# homeboard4.net
KiCad netlist of a schematic drawn in EAGLE
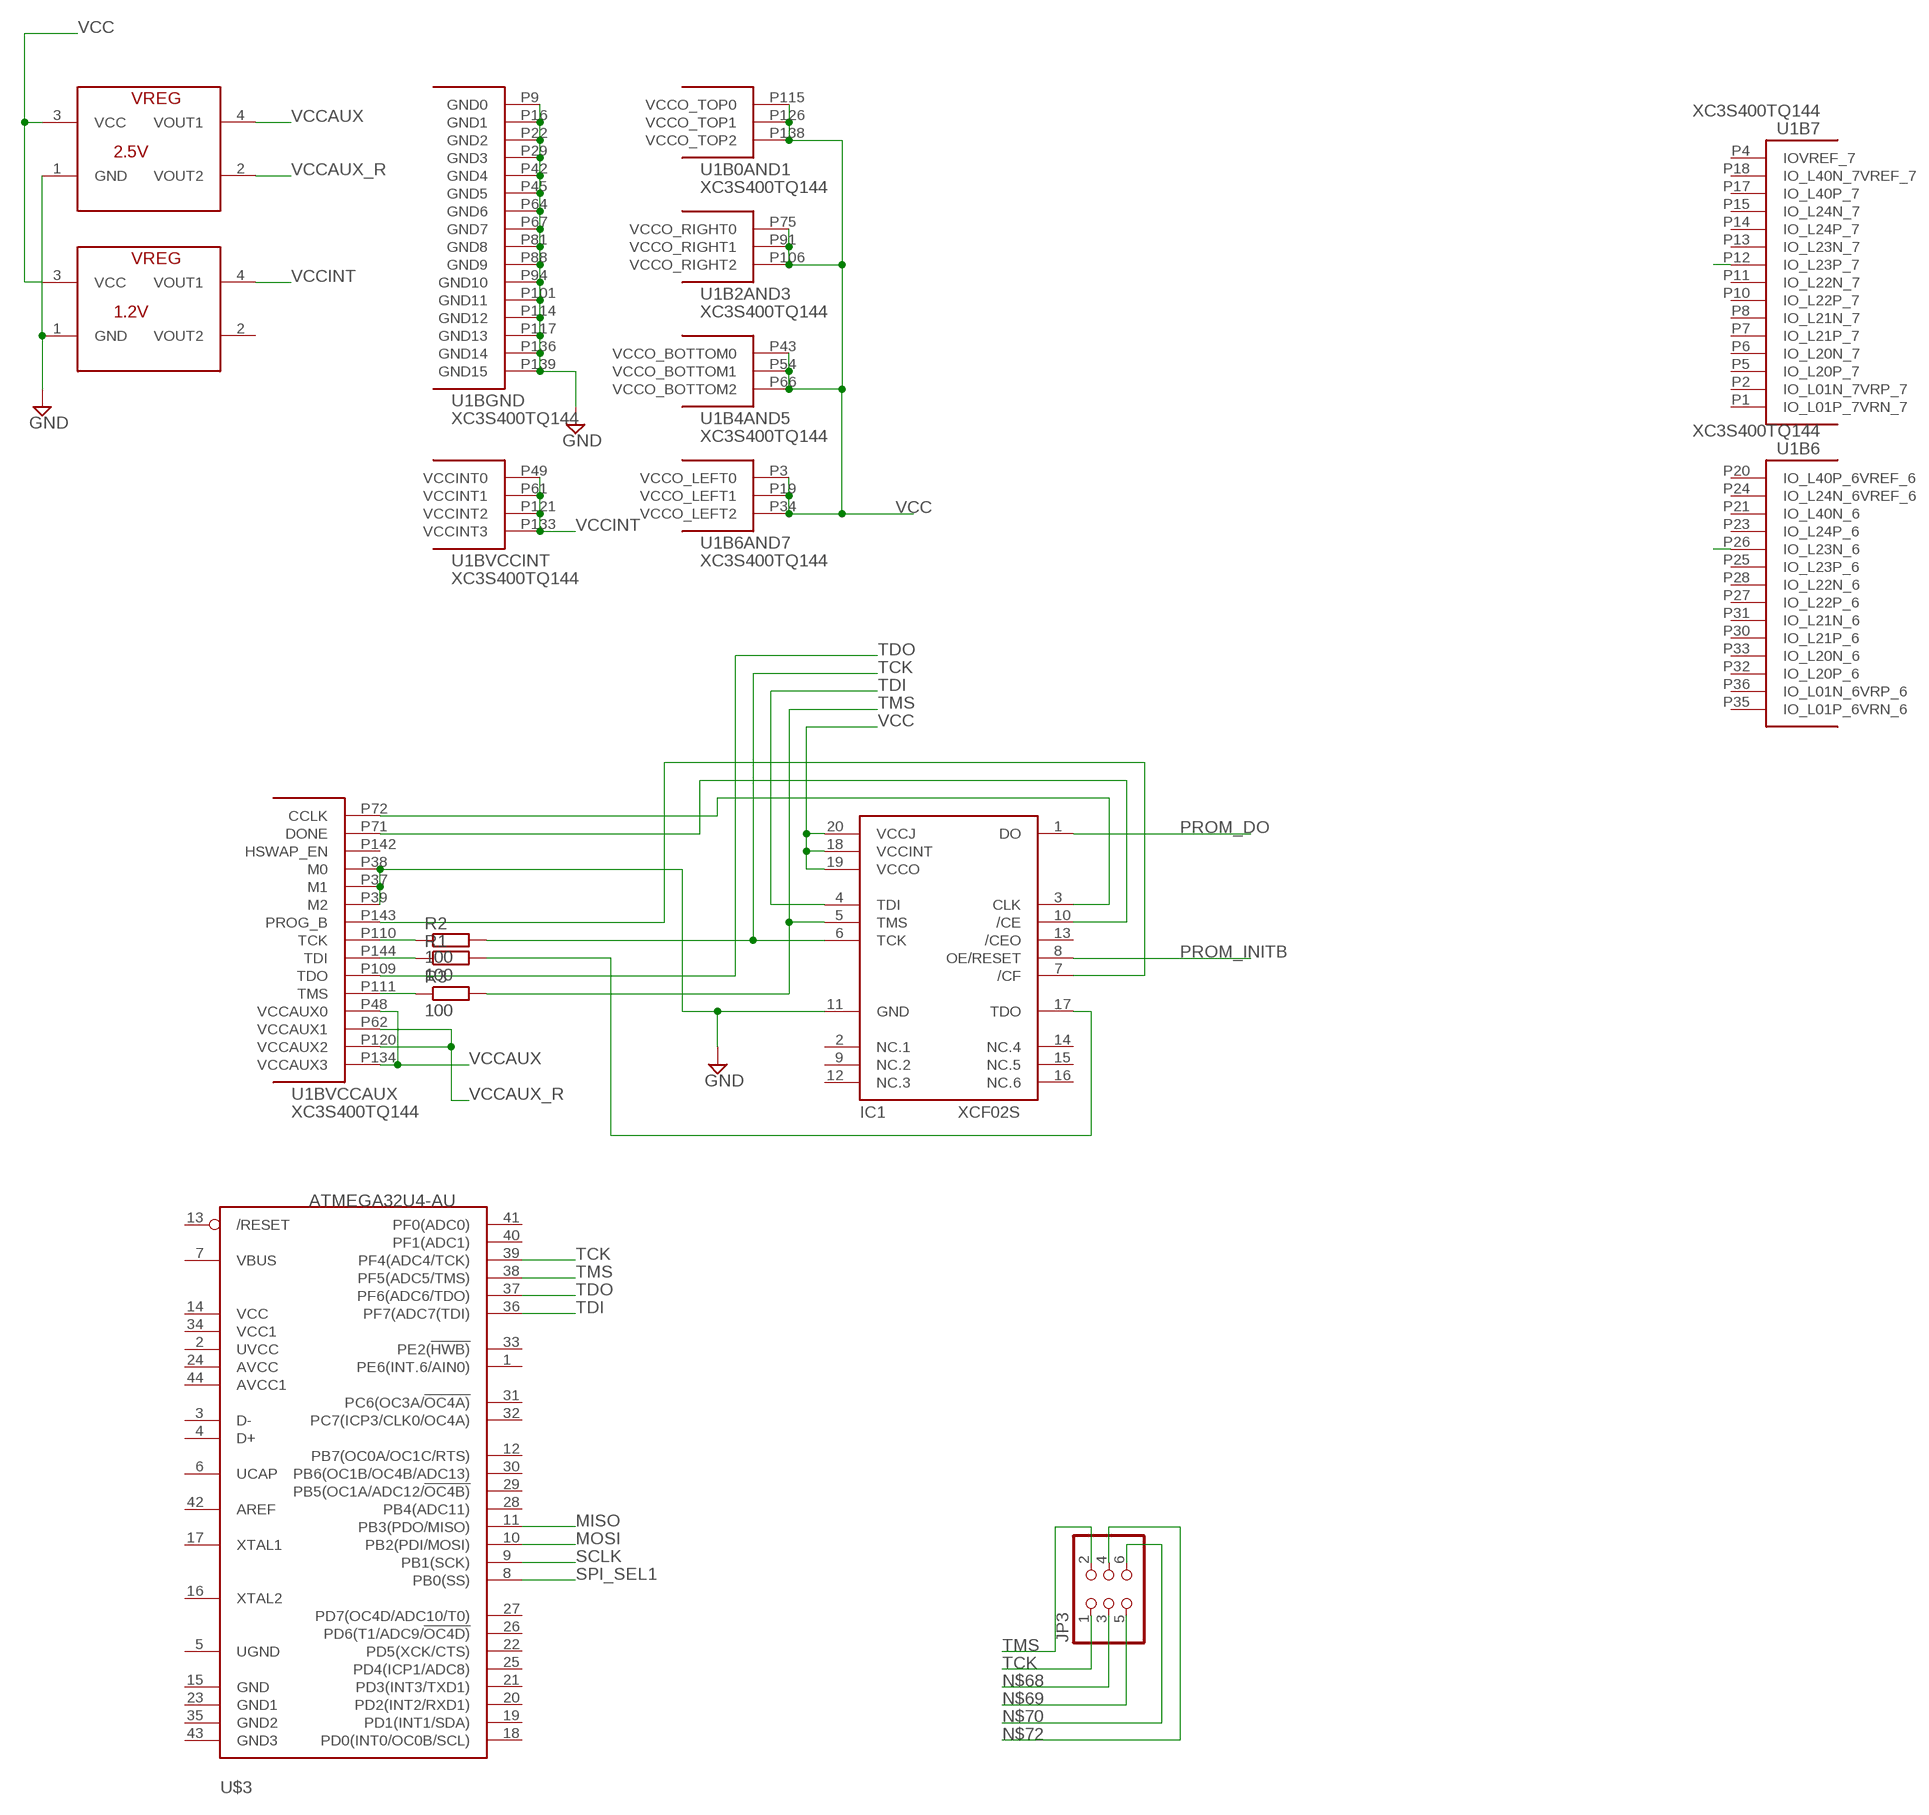
[diagram p0: schematic, sheet 1, part 1 of 3]
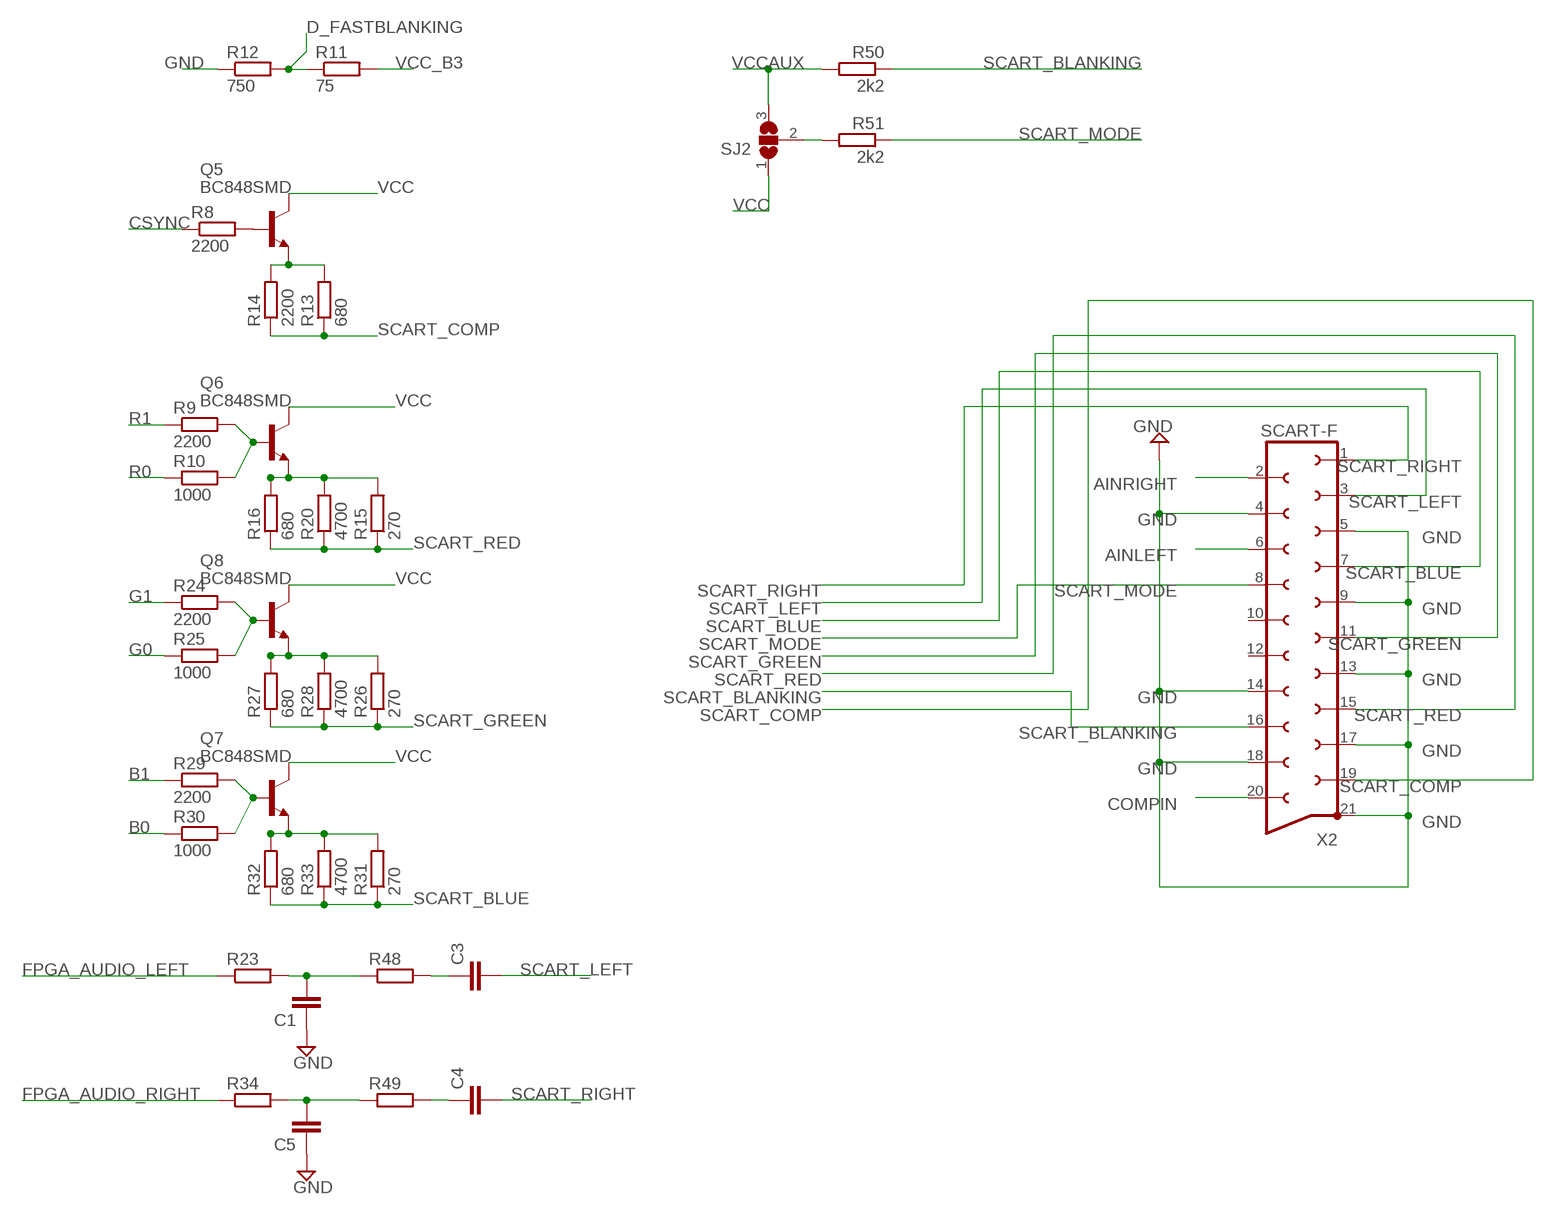
[diagram p1: schematic, sheet 1, part 2 of 3]
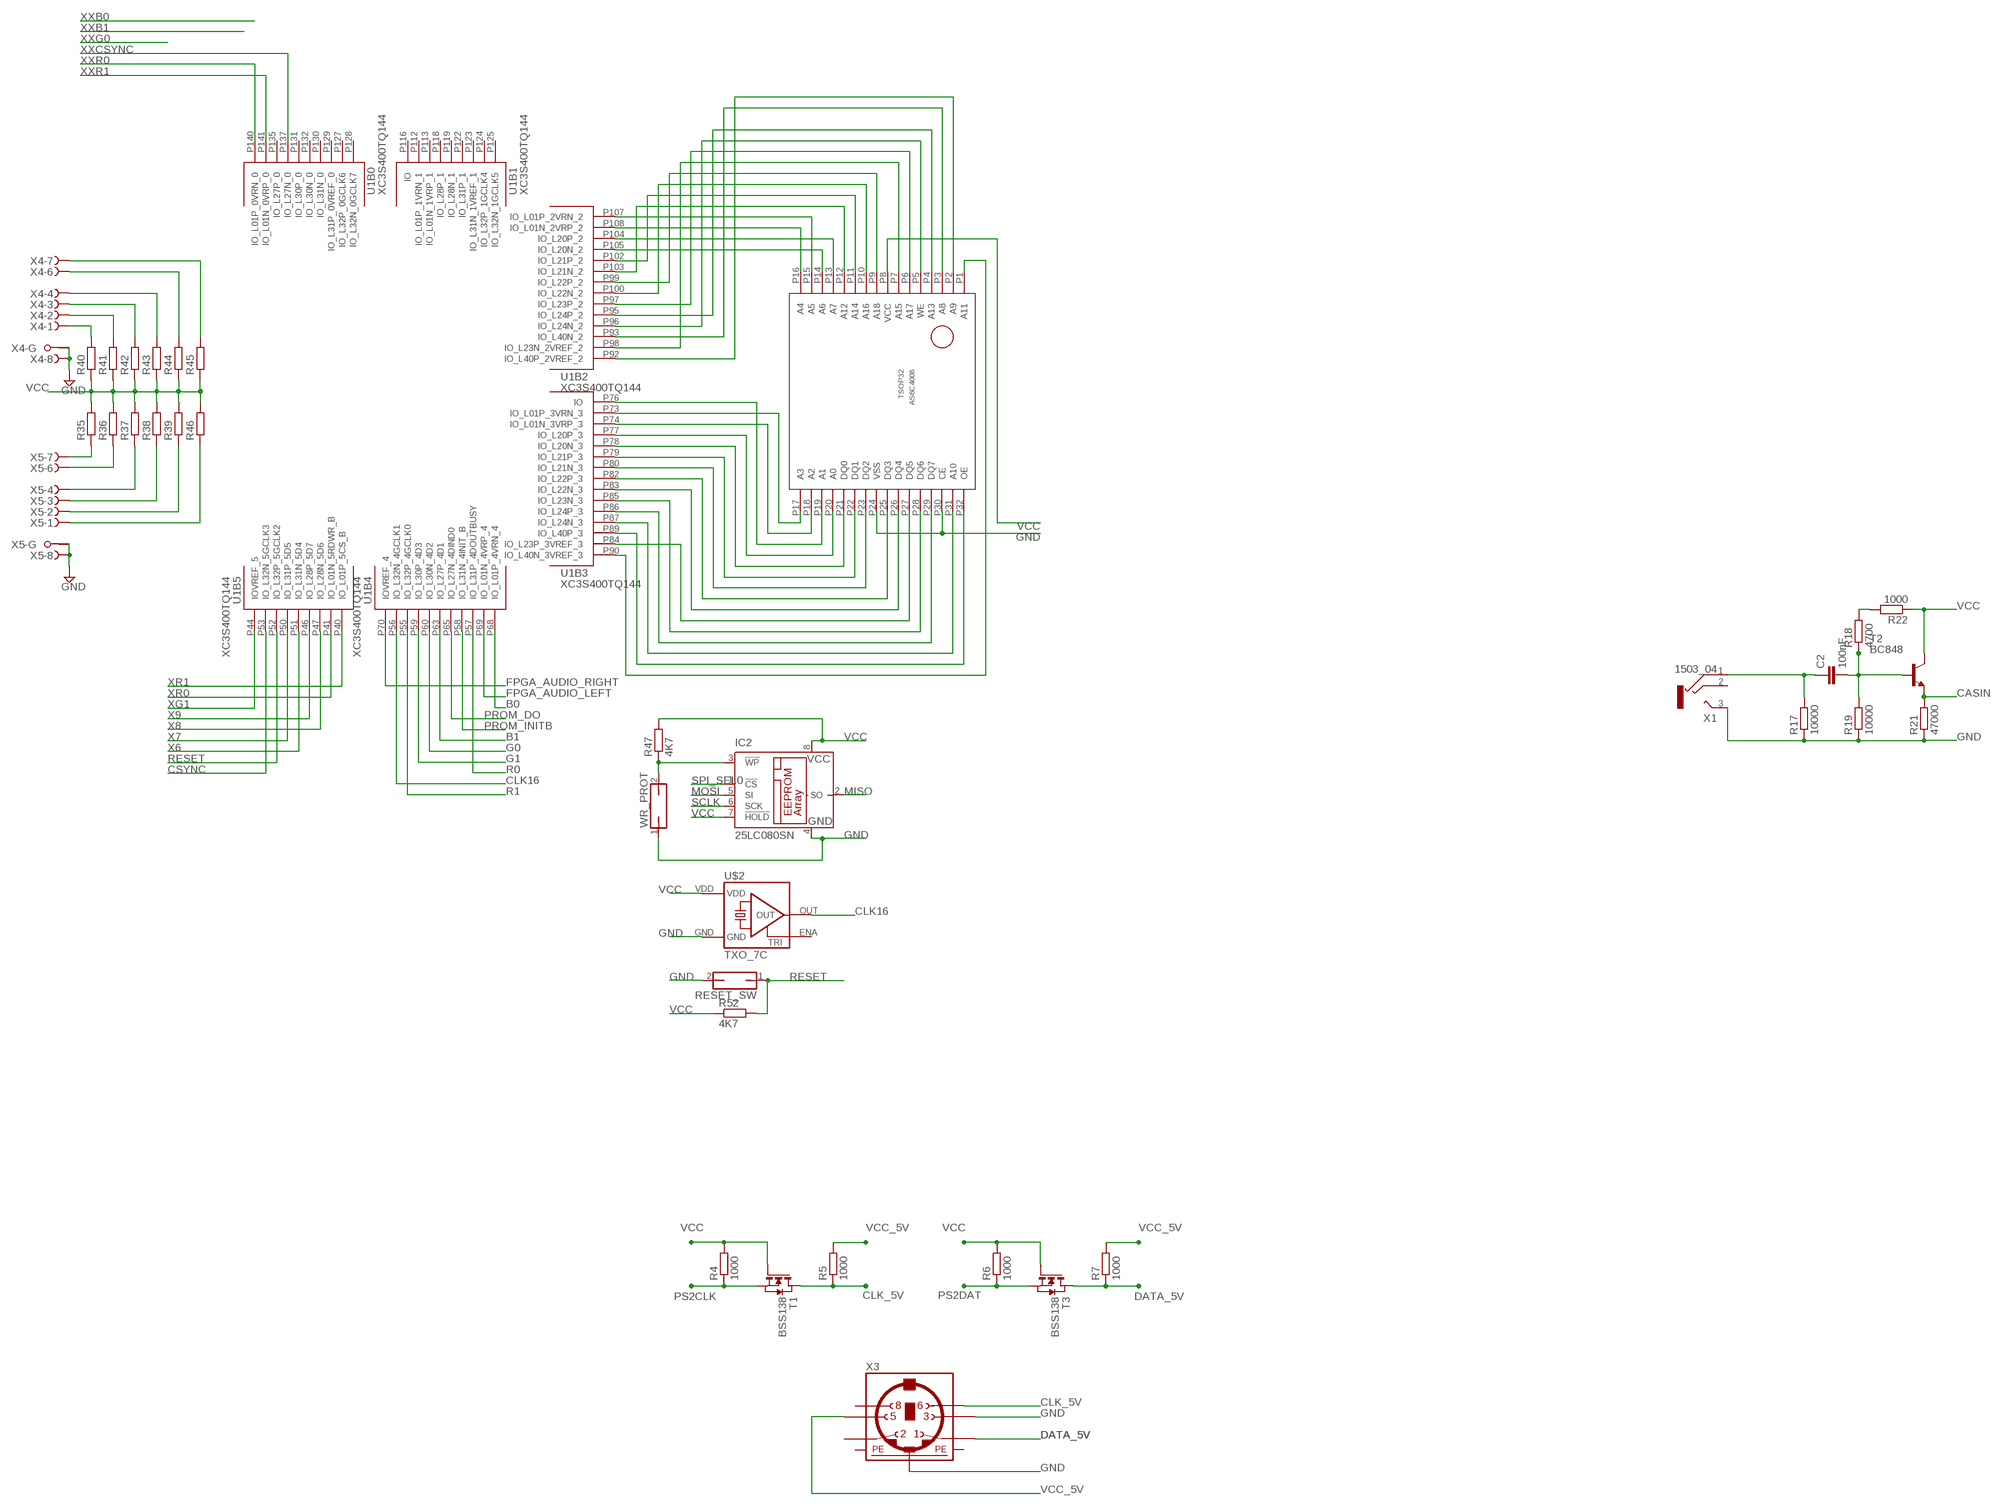
[diagram p2: schematic, sheet 1, part 3 of 3]

(export (version "E")
  (design (tool "Eeschema 10.0.6"))
  (components
    (comp (ref "C1")
      (value "C-EUC0603")
      (footprint "eagle-import:C0603")
      (libsource (lib "eagle-import") (part "C-EUC0603"))
    )
    (comp (ref "C2")
      (value "100nF")
      (footprint "eagle-import:C0603")
      (libsource (lib "eagle-import") (part "C-EUC0603"))
    )
    (comp (ref "C3")
      (value "C-EUC0603")
      (footprint "eagle-import:C0603")
      (libsource (lib "eagle-import") (part "C-EUC0603"))
    )
    (comp (ref "C4")
      (value "C-EUC0603")
      (footprint "eagle-import:C0603")
      (libsource (lib "eagle-import") (part "C-EUC0603"))
    )
    (comp (ref "C5")
      (value "C-EUC0603")
      (footprint "eagle-import:C0603")
      (libsource (lib "eagle-import") (part "C-EUC0603"))
    )
    (comp (ref "IC1")
      (value "XCF02S")
      (footprint "eagle-import:VO20")
      (libsource (lib "eagle-import") (part "XCF02S"))
    )
    (comp (ref "IC2")
      (value "25LC080SN")
      (footprint "eagle-import:SO-08")
      (fields (field (name "MF") "MICROCHIP") (field (name "MPN") "25LC080/SN"))
      (libsource (lib "eagle-import") (part "25SNLC080"))
    )
    (comp (ref "JP3")
      (value "PINHD-2X3")
      (footprint "eagle-import:2X03")
      (libsource (lib "eagle-import") (part "PINHD-2X3"))
    )
    (comp (ref "Q5")
      (value "BC848SMD")
      (footprint "eagle-import:SOT23")
      (libsource (lib "eagle-import") (part "BC848SMD"))
    )
    (comp (ref "Q6")
      (value "BC848SMD")
      (footprint "eagle-import:SOT23")
      (libsource (lib "eagle-import") (part "BC848SMD"))
    )
    (comp (ref "Q7")
      (value "BC848SMD")
      (footprint "eagle-import:SOT23")
      (libsource (lib "eagle-import") (part "BC848SMD"))
    )
    (comp (ref "Q8")
      (value "BC848SMD")
      (footprint "eagle-import:SOT23")
      (libsource (lib "eagle-import") (part "BC848SMD"))
    )
    (comp (ref "R1")
      (value "100")
      (footprint "eagle-import:R0805")
      (libsource (lib "eagle-import") (part "R-EU_R0805"))
    )
    (comp (ref "R2")
      (value "100")
      (footprint "eagle-import:R0805")
      (libsource (lib "eagle-import") (part "R-EU_R0805"))
    )
    (comp (ref "R3")
      (value "100")
      (footprint "eagle-import:R0805")
      (libsource (lib "eagle-import") (part "R-EU_R0805"))
    )
    (comp (ref "R4")
      (value "1000")
      (footprint "eagle-import:R0805")
      (libsource (lib "eagle-import") (part "R-EU_R0805"))
    )
    (comp (ref "R5")
      (value "1000")
      (footprint "eagle-import:R0805")
      (libsource (lib "eagle-import") (part "R-EU_R0805"))
    )
    (comp (ref "R6")
      (value "1000")
      (footprint "eagle-import:R0805")
      (libsource (lib "eagle-import") (part "R-EU_R0805"))
    )
    (comp (ref "R7")
      (value "1000")
      (footprint "eagle-import:R0805")
      (libsource (lib "eagle-import") (part "R-EU_R0805"))
    )
    (comp (ref "R8")
      (value "2200")
      (footprint "eagle-import:R0805")
      (libsource (lib "eagle-import") (part "R-EU_R0805"))
    )
    (comp (ref "R9")
      (value "2200")
      (footprint "eagle-import:R0805")
      (libsource (lib "eagle-import") (part "R-EU_R0805"))
    )
    (comp (ref "R10")
      (value "1000")
      (footprint "eagle-import:R0805")
      (libsource (lib "eagle-import") (part "R-EU_R0805"))
    )
    (comp (ref "R11")
      (value "75")
      (footprint "eagle-import:R0805")
      (libsource (lib "eagle-import") (part "R-EU_R0805"))
    )
    (comp (ref "R12")
      (value "750")
      (footprint "eagle-import:R0805")
      (libsource (lib "eagle-import") (part "R-EU_R0805"))
    )
    (comp (ref "R13")
      (value "680")
      (footprint "eagle-import:R0805")
      (libsource (lib "eagle-import") (part "R-EU_R0805"))
    )
    (comp (ref "R14")
      (value "2200")
      (footprint "eagle-import:R0805")
      (libsource (lib "eagle-import") (part "R-EU_R0805"))
    )
    (comp (ref "R15")
      (value "270")
      (footprint "eagle-import:R0805")
      (libsource (lib "eagle-import") (part "R-EU_R0805"))
    )
    (comp (ref "R16")
      (value "680")
      (footprint "eagle-import:R0805")
      (libsource (lib "eagle-import") (part "R-EU_R0805"))
    )
    (comp (ref "R17")
      (value "10000")
      (footprint "eagle-import:R0805")
      (libsource (lib "eagle-import") (part "R-EU_R0805"))
    )
    (comp (ref "R18")
      (value "4700")
      (footprint "eagle-import:R0805")
      (libsource (lib "eagle-import") (part "R-EU_R0805"))
    )
    (comp (ref "R19")
      (value "10000")
      (footprint "eagle-import:R0805")
      (libsource (lib "eagle-import") (part "R-EU_R0805"))
    )
    (comp (ref "R20")
      (value "4700")
      (footprint "eagle-import:R0805")
      (libsource (lib "eagle-import") (part "R-EU_R0805"))
    )
    (comp (ref "R21")
      (value "47000")
      (footprint "eagle-import:R0805")
      (libsource (lib "eagle-import") (part "R-EU_R0805"))
    )
    (comp (ref "R22")
      (value "1000")
      (footprint "eagle-import:R0805")
      (libsource (lib "eagle-import") (part "R-EU_R0805"))
    )
    (comp (ref "R23")
      (value "R-EU_M0805")
      (footprint "eagle-import:M0805")
      (libsource (lib "eagle-import") (part "resistor_R-EU_M0805"))
    )
    (comp (ref "R24")
      (value "2200")
      (footprint "eagle-import:R0805")
      (libsource (lib "eagle-import") (part "R-EU_R0805"))
    )
    (comp (ref "R25")
      (value "1000")
      (footprint "eagle-import:R0805")
      (libsource (lib "eagle-import") (part "R-EU_R0805"))
    )
    (comp (ref "R26")
      (value "270")
      (footprint "eagle-import:R0805")
      (libsource (lib "eagle-import") (part "R-EU_R0805"))
    )
    (comp (ref "R27")
      (value "680")
      (footprint "eagle-import:R0805")
      (libsource (lib "eagle-import") (part "R-EU_R0805"))
    )
    (comp (ref "R28")
      (value "4700")
      (footprint "eagle-import:R0805")
      (libsource (lib "eagle-import") (part "R-EU_R0805"))
    )
    (comp (ref "R29")
      (value "2200")
      (footprint "eagle-import:R0805")
      (libsource (lib "eagle-import") (part "R-EU_R0805"))
    )
    (comp (ref "R30")
      (value "1000")
      (footprint "eagle-import:R0805")
      (libsource (lib "eagle-import") (part "R-EU_R0805"))
    )
    (comp (ref "R31")
      (value "270")
      (footprint "eagle-import:R0805")
      (libsource (lib "eagle-import") (part "R-EU_R0805"))
    )
    (comp (ref "R32")
      (value "680")
      (footprint "eagle-import:R0805")
      (libsource (lib "eagle-import") (part "R-EU_R0805"))
    )
    (comp (ref "R33")
      (value "4700")
      (footprint "eagle-import:R0805")
      (libsource (lib "eagle-import") (part "R-EU_R0805"))
    )
    (comp (ref "R34")
      (value "R-EU_M0805")
      (footprint "eagle-import:M0805")
      (libsource (lib "eagle-import") (part "resistor_R-EU_M0805"))
    )
    (comp (ref "R35")
      (value "R-EU_M0805")
      (footprint "eagle-import:M0805")
      (libsource (lib "eagle-import") (part "resistor_R-EU_M0805"))
    )
    (comp (ref "R36")
      (value "R-EU_M0805")
      (footprint "eagle-import:M0805")
      (libsource (lib "eagle-import") (part "resistor_R-EU_M0805"))
    )
    (comp (ref "R37")
      (value "R-EU_M0805")
      (footprint "eagle-import:M0805")
      (libsource (lib "eagle-import") (part "resistor_R-EU_M0805"))
    )
    (comp (ref "R38")
      (value "R-EU_M0805")
      (footprint "eagle-import:M0805")
      (libsource (lib "eagle-import") (part "resistor_R-EU_M0805"))
    )
    (comp (ref "R39")
      (value "R-EU_M0805")
      (footprint "eagle-import:M0805")
      (libsource (lib "eagle-import") (part "resistor_R-EU_M0805"))
    )
    (comp (ref "R40")
      (value "R-EU_M0805")
      (footprint "eagle-import:M0805")
      (libsource (lib "eagle-import") (part "resistor_R-EU_M0805"))
    )
    (comp (ref "R41")
      (value "R-EU_M0805")
      (footprint "eagle-import:M0805")
      (libsource (lib "eagle-import") (part "resistor_R-EU_M0805"))
    )
    (comp (ref "R42")
      (value "R-EU_M0805")
      (footprint "eagle-import:M0805")
      (libsource (lib "eagle-import") (part "resistor_R-EU_M0805"))
    )
    (comp (ref "R43")
      (value "R-EU_M0805")
      (footprint "eagle-import:M0805")
      (libsource (lib "eagle-import") (part "resistor_R-EU_M0805"))
    )
    (comp (ref "R44")
      (value "R-EU_M0805")
      (footprint "eagle-import:M0805")
      (libsource (lib "eagle-import") (part "resistor_R-EU_M0805"))
    )
    (comp (ref "R45")
      (value "R-EU_M0805")
      (footprint "eagle-import:M0805")
      (libsource (lib "eagle-import") (part "resistor_R-EU_M0805"))
    )
    (comp (ref "R46")
      (value "R-EU_M0805")
      (footprint "eagle-import:M0805")
      (libsource (lib "eagle-import") (part "resistor_R-EU_M0805"))
    )
    (comp (ref "R47")
      (value "4K7")
      (footprint "eagle-import:R0805")
      (libsource (lib "eagle-import") (part "R-EU_R0805"))
    )
    (comp (ref "R48")
      (value "R-EU_M0805")
      (footprint "eagle-import:M0805")
      (libsource (lib "eagle-import") (part "resistor_R-EU_M0805"))
    )
    (comp (ref "R49")
      (value "R-EU_M0805")
      (footprint "eagle-import:M0805")
      (libsource (lib "eagle-import") (part "resistor_R-EU_M0805"))
    )
    (comp (ref "R50")
      (value "2k2")
      (footprint "eagle-import:M0805")
      (libsource (lib "eagle-import") (part "resistor_R-EU_M0805"))
    )
    (comp (ref "R51")
      (value "2k2")
      (footprint "eagle-import:M0805")
      (libsource (lib "eagle-import") (part "resistor_R-EU_M0805"))
    )
    (comp (ref "R52")
      (value "4K7")
      (footprint "eagle-import:M0805")
      (libsource (lib "eagle-import") (part "resistor_R-EU_M0805"))
    )
    (comp (ref "REG1.2")
      (value "1.2V")
      (footprint "eagle-import:SOT223")
      (libsource (lib "eagle-import") (part "NX1117"))
    )
    (comp (ref "REG2.5")
      (value "2.5V")
      (footprint "eagle-import:SOT223")
      (libsource (lib "eagle-import") (part "NX1117"))
    )
    (comp (ref "RESET_SW")
      (value "JP1Q")
      (footprint "eagle-import:JP1")
      (libsource (lib "eagle-import") (part "JP1Q"))
    )
    (comp (ref "SJ2")
      (value "SJ2W")
      (footprint "eagle-import:SJ_2")
      (libsource (lib "eagle-import") (part "SJ2W"))
    )
    (comp (ref "T1")
      (value "BSS138")
      (footprint "eagle-import:SOT-23")
      (libsource (lib "eagle-import") (part "NMOSSOT23"))
    )
    (comp (ref "T2")
      (value "BC848")
      (footprint "eagle-import:SOT23")
      (libsource (lib "eagle-import") (part "BC848"))
    )
    (comp (ref "T3")
      (value "BSS138")
      (footprint "eagle-import:SOT-23")
      (libsource (lib "eagle-import") (part "NMOSSOT23"))
    )
    (comp (ref "U$1")
      (value "AS6C4008")
      (footprint "eagle-import:TSOP32")
      (libsource (lib "eagle-import") (part "AS6C4008"))
    )
    (comp (ref "U$2")
      (value "TXO_7C")
      (footprint "eagle-import:OSC_7C")
      (libsource (lib "eagle-import") (part "TXO_7C"))
    )
    (comp (ref "U$3")
      (value "ATMEGA32U4-AU")
      (footprint "eagle-import:TQFP44")
      (libsource (lib "eagle-import") (part "ATMEGA32U4-AU"))
    )
    (comp (ref "U1")
      (value "XC3S400TQ144")
      (footprint "eagle-import:TQ144")
      (libsource (lib "eagle-import") (part "XC3S400TQ144"))
    )
    (comp (ref "WR_PROT")
      (value "JP1Q")
      (footprint "eagle-import:JP1")
      (libsource (lib "eagle-import") (part "JP1Q"))
    )
    (comp (ref "X1")
      (value "1503_04")
      (footprint "eagle-import:1503_04")
      (libsource (lib "eagle-import") (part "1503_04"))
    )
    (comp (ref "X2")
      (value "SCART-F")
      (footprint "eagle-import:SCART-F")
      (libsource (lib "eagle-import") (part "SCART-F"))
    )
    (comp (ref "X3")
      (value "MINI_DIN_6")
      (footprint "eagle-import:M_DIN6")
      (libsource (lib "eagle-import") (part "MINI_DIN_6"))
    )
    (comp (ref "X4")
      (value "F09HPS")
      (footprint "eagle-import:F09HP")
      (libsource (lib "eagle-import") (part "F09HPS"))
    )
    (comp (ref "X5")
      (value "F09HPS")
      (footprint "eagle-import:F09HP")
      (libsource (lib "eagle-import") (part "F09HPS"))
    )
  )
  (nets
    (net (code "1") (name "/AINLEFT") (class "Default")
      (node (ref "X2") (pin "6") (pinfunction "6_6") (pintype "passive"))
    )
    (net (code "2") (name "/AINRIGHT") (class "Default")
      (node (ref "X2") (pin "2") (pinfunction "2_2") (pintype "passive"))
    )
    (net (code "3") (name "/B0") (class "Default")
      (node (ref "R30") (pin "1") (pinfunction "1_1") (pintype "passive"))
      (node (ref "U1") (pin "P68") (pinfunction "IO_L01P_4VRN_4_P68") (pintype "bidirectional"))
    )
    (net (code "4") (name "/B1") (class "Default")
      (node (ref "R29") (pin "1") (pinfunction "1_1") (pintype "passive"))
      (node (ref "U1") (pin "P63") (pinfunction "IO_L27P_4D1_P63") (pintype "bidirectional"))
    )
    (net (code "5") (name "/CASIN") (class "Default")
      (node (ref "R21") (pin "2") (pinfunction "2_2") (pintype "passive"))
      (node (ref "T2") (pin "2") (pinfunction "E_2") (pintype "passive"))
    )
    (net (code "6") (name "/CLK16") (class "Default")
      (node (ref "U$2") (pin "OUT") (pinfunction "OUT_OUT") (pintype "output"))
      (node (ref "U1") (pin "P56") (pinfunction "IO_L32N_4GCLK1_P56") (pintype "bidirectional"))
    )
    (net (code "7") (name "/CLK_5V") (class "Default")
      (node (ref "R5") (pin "1") (pinfunction "1_1") (pintype "passive"))
      (node (ref "T1") (pin "1") (pinfunction "D_1") (pintype "passive"))
      (node (ref "X3") (pin "6") (pinfunction "6_6") (pintype "passive"))
    )
    (net (code "8") (name "/COMPIN") (class "Default")
      (node (ref "X2") (pin "20") (pinfunction "20_20") (pintype "passive"))
    )
    (net (code "9") (name "/CSYNC") (class "Default")
      (node (ref "R8") (pin "1") (pinfunction "1_1") (pintype "passive"))
      (node (ref "U1") (pin "P53") (pinfunction "IO_L32N_5GCLK3_P53") (pintype "bidirectional"))
    )
    (net (code "10") (name "/DATA_5V") (class "Default")
      (node (ref "R7") (pin "1") (pinfunction "1_1") (pintype "passive"))
      (node (ref "T3") (pin "1") (pinfunction "D_1") (pintype "passive"))
      (node (ref "X3") (pin "1") (pinfunction "1_1") (pintype "passive"))
    )
    (net (code "11") (name "/D_FASTBLANKING") (class "Default")
      (node (ref "R11") (pin "1") (pinfunction "1_1") (pintype "passive"))
      (node (ref "R12") (pin "2") (pinfunction "2_2") (pintype "passive"))
    )
    (net (code "12") (name "/FPGA_AUDIO_LEFT") (class "Default")
      (node (ref "R23") (pin "1") (pinfunction "1_1") (pintype "passive"))
      (node (ref "U1") (pin "P69") (pinfunction "IO_L01N_4VRP_4_P69") (pintype "bidirectional"))
    )
    (net (code "13") (name "/FPGA_AUDIO_RIGHT") (class "Default")
      (node (ref "R34") (pin "1") (pinfunction "1_1") (pintype "passive"))
      (node (ref "U1") (pin "P70") (pinfunction "IOVREF_4_P70") (pintype "bidirectional"))
    )
    (net (code "14") (name "/G0") (class "Default")
      (node (ref "R25") (pin "1") (pinfunction "1_1") (pintype "passive"))
      (node (ref "U1") (pin "P60") (pinfunction "IO_L30N_4D2_P60") (pintype "bidirectional"))
    )
    (net (code "15") (name "/G1") (class "Default")
      (node (ref "R24") (pin "1") (pinfunction "1_1") (pintype "passive"))
      (node (ref "U1") (pin "P59") (pinfunction "IO_L30P_4D3_P59") (pintype "bidirectional"))
    )
    (net (code "16") (name "/MISO") (class "Default")
      (node (ref "IC2") (pin "2") (pinfunction "SO_2") (pintype "bidirectional"))
      (node (ref "U$3") (pin "11") (pinfunction "PB3(PDO/MISO)_11") (pintype "bidirectional"))
    )
    (net (code "17") (name "/MOSI") (class "Default")
      (node (ref "IC2") (pin "5") (pinfunction "SI_5") (pintype "input"))
      (node (ref "U$3") (pin "10") (pinfunction "PB2(PDI/MOSI)_10") (pintype "bidirectional"))
    )
    (net (code "18") (name "/N$68") (class "Default")
      (node (ref "JP3") (pin "3") (pinfunction "3_3") (pintype "passive"))
    )
    (net (code "19") (name "/N$69") (class "Default")
      (node (ref "JP3") (pin "5") (pinfunction "5_5") (pintype "passive"))
    )
    (net (code "20") (name "/N$70") (class "Default")
      (node (ref "JP3") (pin "6") (pinfunction "6_6") (pintype "passive"))
    )
    (net (code "21") (name "/N$72") (class "Default")
      (node (ref "JP3") (pin "4") (pinfunction "4_4") (pintype "passive"))
    )
    (net (code "22") (name "/PE1") (class "Default")
      (node (ref "X3") (pin "SH1") (pinfunction "PE1_SH1") (pintype "power_in"))
    )
    (net (code "23") (name "/PE3") (class "Default")
      (node (ref "X3") (pin "SH3") (pinfunction "PE3_SH3") (pintype "power_in"))
    )
    (net (code "24") (name "/PROM_DO") (class "Default")
      (node (ref "IC1") (pin "1") (pinfunction "DO_1") (pintype "bidirectional"))
      (node (ref "U1") (pin "P65") (pinfunction "IO_L27N_4DIND0_P65") (pintype "bidirectional"))
    )
    (net (code "25") (name "/PROM_INITB") (class "Default")
      (node (ref "IC1") (pin "8") (pinfunction "OE/RESET_8") (pintype "bidirectional"))
      (node (ref "U1") (pin "P58") (pinfunction "IO_L31N_4INIT_B_P58") (pintype "bidirectional"))
    )
    (net (code "26") (name "/PS2CLK") (class "Default")
      (node (ref "R4") (pin "1") (pinfunction "1_1") (pintype "passive"))
      (node (ref "T1") (pin "2") (pinfunction "S_2") (pintype "passive"))
    )
    (net (code "27") (name "/PS2DAT") (class "Default")
      (node (ref "R6") (pin "1") (pinfunction "1_1") (pintype "passive"))
      (node (ref "T3") (pin "2") (pinfunction "S_2") (pintype "passive"))
    )
    (net (code "28") (name "/R0") (class "Default")
      (node (ref "R10") (pin "1") (pinfunction "1_1") (pintype "passive"))
      (node (ref "U1") (pin "P57") (pinfunction "IO_L31P_4DOUTBUSY_P57") (pintype "bidirectional"))
    )
    (net (code "29") (name "/R1") (class "Default")
      (node (ref "R9") (pin "1") (pinfunction "1_1") (pintype "passive"))
      (node (ref "U1") (pin "P55") (pinfunction "IO_L32P_4GCLK0_P55") (pintype "bidirectional"))
    )
    (net (code "30") (name "/RESET") (class "Default")
      (node (ref "R52") (pin "2") (pinfunction "2_2") (pintype "passive"))
      (node (ref "RESET_SW") (pin "1") (pinfunction "1_1") (pintype "passive"))
      (node (ref "U1") (pin "P52") (pinfunction "IO_L32P_5GCLK2_P52") (pintype "bidirectional"))
    )
    (net (code "31") (name "/SCART_BLANKING") (class "Default")
      (node (ref "R50") (pin "1") (pinfunction "1_1") (pintype "passive"))
      (node (ref "X2") (pin "16") (pinfunction "16_16") (pintype "passive"))
    )
    (net (code "32") (name "/SCART_BLUE") (class "Default")
      (node (ref "R31") (pin "1") (pinfunction "1_1") (pintype "passive"))
      (node (ref "R32") (pin "1") (pinfunction "1_1") (pintype "passive"))
      (node (ref "R33") (pin "1") (pinfunction "1_1") (pintype "passive"))
      (node (ref "X2") (pin "7") (pinfunction "7_7") (pintype "passive"))
    )
    (net (code "33") (name "/SCART_COMP") (class "Default")
      (node (ref "R13") (pin "1") (pinfunction "1_1") (pintype "passive"))
      (node (ref "R14") (pin "1") (pinfunction "1_1") (pintype "passive"))
      (node (ref "X2") (pin "19") (pinfunction "19_19") (pintype "passive"))
    )
    (net (code "34") (name "/SCART_GREEN") (class "Default")
      (node (ref "R26") (pin "1") (pinfunction "1_1") (pintype "passive"))
      (node (ref "R27") (pin "1") (pinfunction "1_1") (pintype "passive"))
      (node (ref "R28") (pin "1") (pinfunction "1_1") (pintype "passive"))
      (node (ref "X2") (pin "11") (pinfunction "11_11") (pintype "passive"))
    )
    (net (code "35") (name "/SCART_LEFT") (class "Default")
      (node (ref "C3") (pin "2") (pinfunction "2_2") (pintype "passive"))
      (node (ref "X2") (pin "3") (pinfunction "3_3") (pintype "passive"))
    )
    (net (code "36") (name "/SCART_MODE") (class "Default")
      (node (ref "R51") (pin "1") (pinfunction "1_1") (pintype "passive"))
      (node (ref "X2") (pin "8") (pinfunction "8_8") (pintype "passive"))
    )
    (net (code "37") (name "/SCART_RED") (class "Default")
      (node (ref "R15") (pin "1") (pinfunction "1_1") (pintype "passive"))
      (node (ref "R16") (pin "1") (pinfunction "1_1") (pintype "passive"))
      (node (ref "R20") (pin "1") (pinfunction "1_1") (pintype "passive"))
      (node (ref "X2") (pin "15") (pinfunction "15_15") (pintype "passive"))
    )
    (net (code "38") (name "/SCART_RIGHT") (class "Default")
      (node (ref "C4") (pin "2") (pinfunction "2_2") (pintype "passive"))
      (node (ref "X2") (pin "1") (pinfunction "1_1") (pintype "passive"))
    )
    (net (code "39") (name "/SCLK") (class "Default")
      (node (ref "IC2") (pin "6") (pinfunction "SCK_6") (pintype "input"))
      (node (ref "U$3") (pin "9") (pinfunction "PB1(SCK)_9") (pintype "bidirectional"))
    )
    (net (code "40") (name "/SPI_SEL0") (class "Default")
      (node (ref "IC2") (pin "1") (pinfunction "~{CS}_1") (pintype "input"))
    )
    (net (code "41") (name "/SPI_SEL1") (class "Default")
      (node (ref "U$3") (pin "8") (pinfunction "PB0(SS)_8") (pintype "bidirectional"))
    )
    (net (code "42") (name "/TCK") (class "Default")
      (node (ref "IC1") (pin "6") (pinfunction "TCK_6") (pintype "bidirectional"))
      (node (ref "JP3") (pin "1") (pinfunction "1_1") (pintype "passive"))
      (node (ref "R2") (pin "2") (pinfunction "2_2") (pintype "passive"))
      (node (ref "U$3") (pin "39") (pinfunction "PF4(ADC4/TCK)_39") (pintype "bidirectional"))
    )
    (net (code "43") (name "/TDI") (class "Default")
      (node (ref "IC1") (pin "4") (pinfunction "TDI_4") (pintype "bidirectional"))
      (node (ref "U$3") (pin "36") (pinfunction "PF7(ADC7(TDI)_36") (pintype "bidirectional"))
    )
    (net (code "44") (name "/TDO") (class "Default")
      (node (ref "U$3") (pin "37") (pinfunction "PF6(ADC6/TDO)_37") (pintype "bidirectional"))
      (node (ref "U1") (pin "P109") (pinfunction "TDO_P109") (pintype "bidirectional"))
    )
    (net (code "45") (name "/TMS") (class "Default")
      (node (ref "IC1") (pin "5") (pinfunction "TMS_5") (pintype "bidirectional"))
      (node (ref "JP3") (pin "2") (pinfunction "2_2") (pintype "passive"))
      (node (ref "R3") (pin "2") (pinfunction "2_2") (pintype "passive"))
      (node (ref "U$3") (pin "38") (pinfunction "PF5(ADC5/TMS)_38") (pintype "bidirectional"))
    )
    (net (code "46") (name "/VCC") (class "Default")
      (node (ref "IC1") (pin "18") (pinfunction "VCCINT_18") (pintype "bidirectional"))
      (node (ref "IC1") (pin "19") (pinfunction "VCCO_19") (pintype "bidirectional"))
      (node (ref "IC1") (pin "20") (pinfunction "VCCJ_20") (pintype "bidirectional"))
      (node (ref "IC2") (pin "7") (pinfunction "~{HOLD}_7") (pintype "input"))
      (node (ref "IC2") (pin "8") (pinfunction "VCC_8") (pintype "power_in"))
      (node (ref "Q5") (pin "3") (pinfunction "C_3") (pintype "passive"))
      (node (ref "Q6") (pin "3") (pinfunction "C_3") (pintype "passive"))
      (node (ref "Q7") (pin "3") (pinfunction "C_3") (pintype "passive"))
      (node (ref "Q8") (pin "3") (pinfunction "C_3") (pintype "passive"))
      (node (ref "R22") (pin "1") (pinfunction "1_1") (pintype "passive"))
      (node (ref "R35") (pin "2") (pinfunction "2_2") (pintype "passive"))
      (node (ref "R36") (pin "2") (pinfunction "2_2") (pintype "passive"))
      (node (ref "R37") (pin "2") (pinfunction "2_2") (pintype "passive"))
      (node (ref "R38") (pin "2") (pinfunction "2_2") (pintype "passive"))
      (node (ref "R39") (pin "2") (pinfunction "2_2") (pintype "passive"))
      (node (ref "R4") (pin "2") (pinfunction "2_2") (pintype "passive"))
      (node (ref "R40") (pin "1") (pinfunction "1_1") (pintype "passive"))
      (node (ref "R41") (pin "1") (pinfunction "1_1") (pintype "passive"))
      (node (ref "R42") (pin "1") (pinfunction "1_1") (pintype "passive"))
      (node (ref "R43") (pin "1") (pinfunction "1_1") (pintype "passive"))
      (node (ref "R44") (pin "1") (pinfunction "1_1") (pintype "passive"))
      (node (ref "R45") (pin "1") (pinfunction "1_1") (pintype "passive"))
      (node (ref "R46") (pin "2") (pinfunction "2_2") (pintype "passive"))
      (node (ref "R47") (pin "2") (pinfunction "2_2") (pintype "passive"))
      (node (ref "R52") (pin "1") (pinfunction "1_1") (pintype "passive"))
      (node (ref "R6") (pin "2") (pinfunction "2_2") (pintype "passive"))
      (node (ref "REG1.2") (pin "3") (pinfunction "VCC_3") (pintype "bidirectional"))
      (node (ref "REG2.5") (pin "3") (pinfunction "VCC_3") (pintype "bidirectional"))
      (node (ref "SJ2") (pin "1") (pinfunction "1_1") (pintype "passive"))
      (node (ref "T1") (pin "3") (pinfunction "G_3") (pintype "passive"))
      (node (ref "T2") (pin "3") (pinfunction "C_3") (pintype "passive"))
      (node (ref "T3") (pin "3") (pinfunction "G_3") (pintype "passive"))
      (node (ref "U$1") (pin "P8") (pinfunction "VCC_P8") (pintype "bidirectional"))
      (node (ref "U$2") (pin "VDD") (pinfunction "VDD_VDD") (pintype "power_in"))
      (node (ref "U1") (pin "P106") (pinfunction "VCCO_RIGHT2_P106") (pintype "passive"))
      (node (ref "U1") (pin "P115") (pinfunction "VCCO_TOP0_P115") (pintype "passive"))
      (node (ref "U1") (pin "P126") (pinfunction "VCCO_TOP1_P126") (pintype "passive"))
      (node (ref "U1") (pin "P138") (pinfunction "VCCO_TOP2_P138") (pintype "passive"))
      (node (ref "U1") (pin "P19") (pinfunction "VCCO_LEFT1_P19") (pintype "passive"))
      (node (ref "U1") (pin "P3") (pinfunction "VCCO_LEFT0_P3") (pintype "passive"))
      (node (ref "U1") (pin "P34") (pinfunction "VCCO_LEFT2_P34") (pintype "passive"))
      (node (ref "U1") (pin "P43") (pinfunction "VCCO_BOTTOM0_P43") (pintype "passive"))
      (node (ref "U1") (pin "P54") (pinfunction "VCCO_BOTTOM1_P54") (pintype "passive"))
      (node (ref "U1") (pin "P66") (pinfunction "VCCO_BOTTOM2_P66") (pintype "passive"))
      (node (ref "U1") (pin "P75") (pinfunction "VCCO_RIGHT0_P75") (pintype "passive"))
      (node (ref "U1") (pin "P91") (pinfunction "VCCO_RIGHT1_P91") (pintype "passive"))
    )
    (net (code "47") (name "/VCCAUX") (class "Default")
      (node (ref "R50") (pin "2") (pinfunction "2_2") (pintype "passive"))
      (node (ref "REG2.5") (pin "4") (pinfunction "VOUT1_4") (pintype "bidirectional"))
      (node (ref "SJ2") (pin "3") (pinfunction "3_3") (pintype "passive"))
      (node (ref "U1") (pin "P134") (pinfunction "VCCAUX3_P134") (pintype "passive"))
      (node (ref "U1") (pin "P48") (pinfunction "VCCAUX0_P48") (pintype "passive"))
    )
    (net (code "48") (name "/VCCAUX_R") (class "Default")
      (node (ref "REG2.5") (pin "2") (pinfunction "VOUT2_2") (pintype "bidirectional"))
      (node (ref "U1") (pin "P120") (pinfunction "VCCAUX2_P120") (pintype "passive"))
      (node (ref "U1") (pin "P62") (pinfunction "VCCAUX1_P62") (pintype "passive"))
    )
    (net (code "49") (name "/VCCINT") (class "Default")
      (node (ref "REG1.2") (pin "4") (pinfunction "VOUT1_4") (pintype "bidirectional"))
      (node (ref "U1") (pin "P121") (pinfunction "VCCINT2_P121") (pintype "passive"))
      (node (ref "U1") (pin "P133") (pinfunction "VCCINT3_P133") (pintype "passive"))
      (node (ref "U1") (pin "P49") (pinfunction "VCCINT0_P49") (pintype "passive"))
      (node (ref "U1") (pin "P61") (pinfunction "VCCINT1_P61") (pintype "passive"))
    )
    (net (code "50") (name "/VCC_5V") (class "Default")
      (node (ref "R5") (pin "2") (pinfunction "2_2") (pintype "passive"))
      (node (ref "R7") (pin "2") (pinfunction "2_2") (pintype "passive"))
      (node (ref "X3") (pin "5") (pinfunction "5_5") (pintype "passive"))
    )
    (net (code "51") (name "/VCC_B3") (class "Default")
      (node (ref "R11") (pin "2") (pinfunction "2_2") (pintype "passive"))
    )
    (net (code "52") (name "/X6") (class "Default")
      (node (ref "U1") (pin "P51") (pinfunction "IO_L31N_5D4_P51") (pintype "bidirectional"))
    )
    (net (code "53") (name "/X7") (class "Default")
      (node (ref "U1") (pin "P50") (pinfunction "IO_L31P_5D5_P50") (pintype "bidirectional"))
    )
    (net (code "54") (name "/X8") (class "Default")
      (node (ref "U1") (pin "P47") (pinfunction "IO_L28N_5D6_P47") (pintype "bidirectional"))
    )
    (net (code "55") (name "/X9") (class "Default")
      (node (ref "U1") (pin "P46") (pinfunction "IO_L28P_5D7_P46") (pintype "bidirectional"))
    )
    (net (code "56") (name "/XG1") (class "Default")
      (node (ref "U1") (pin "P44") (pinfunction "IOVREF_5_P44") (pintype "bidirectional"))
    )
    (net (code "57") (name "/XR0") (class "Default")
      (node (ref "U1") (pin "P41") (pinfunction "IO_L01N_5RDWR_B_P41") (pintype "bidirectional"))
    )
    (net (code "58") (name "/XR1") (class "Default")
      (node (ref "U1") (pin "P40") (pinfunction "IO_L01P_5CS_B_P40") (pintype "bidirectional"))
    )
    (net (code "61") (name "/XXCSYNC") (class "Default")
      (node (ref "U1") (pin "P137") (pinfunction "IO_L27N_0_P137") (pintype "bidirectional"))
    )
    (net (code "63") (name "/XXR0") (class "Default")
      (node (ref "U1") (pin "P140") (pinfunction "IO_L01P_0VRN_0_P140") (pintype "bidirectional"))
    )
    (net (code "64") (name "/XXR1") (class "Default")
      (node (ref "U1") (pin "P141") (pinfunction "IO_L01N_0VRP_0_P141") (pintype "bidirectional"))
    )
    (net (code "65") (name "GND") (class "Default")
      (node (ref "C1") (pin "1") (pinfunction "1_1") (pintype "passive"))
      (node (ref "C5") (pin "1") (pinfunction "1_1") (pintype "passive"))
      (node (ref "IC1") (pin "11") (pinfunction "GND_11") (pintype "bidirectional"))
      (node (ref "IC2") (pin "4") (pinfunction "GND_4") (pintype "power_in"))
      (node (ref "R12") (pin "1") (pinfunction "1_1") (pintype "passive"))
      (node (ref "R17") (pin "1") (pinfunction "1_1") (pintype "passive"))
      (node (ref "R19") (pin "1") (pinfunction "1_1") (pintype "passive"))
      (node (ref "R21") (pin "1") (pinfunction "1_1") (pintype "passive"))
      (node (ref "REG1.2") (pin "1") (pinfunction "GND_1") (pintype "bidirectional"))
      (node (ref "REG2.5") (pin "1") (pinfunction "GND_1") (pintype "bidirectional"))
      (node (ref "RESET_SW") (pin "2") (pinfunction "2_2") (pintype "passive"))
      (node (ref "U$1") (pin "P24") (pinfunction "VSS_P24") (pintype "bidirectional"))
      (node (ref "U$1") (pin "P30") (pinfunction "CE_P30") (pintype "bidirectional"))
      (node (ref "U$2") (pin "GND") (pinfunction "GND_GND") (pintype "power_in"))
      (node (ref "U1") (pin "P101") (pinfunction "GND11_P101") (pintype "passive"))
      (node (ref "U1") (pin "P114") (pinfunction "GND12_P114") (pintype "passive"))
      (node (ref "U1") (pin "P117") (pinfunction "GND13_P117") (pintype "passive"))
      (node (ref "U1") (pin "P136") (pinfunction "GND14_P136") (pintype "passive"))
      (node (ref "U1") (pin "P139") (pinfunction "GND15_P139") (pintype "passive"))
      (node (ref "U1") (pin "P16") (pinfunction "GND1_P16") (pintype "passive"))
      (node (ref "U1") (pin "P22") (pinfunction "GND2_P22") (pintype "passive"))
      (node (ref "U1") (pin "P29") (pinfunction "GND3_P29") (pintype "passive"))
      (node (ref "U1") (pin "P37") (pinfunction "M1_P37") (pintype "bidirectional"))
      (node (ref "U1") (pin "P38") (pinfunction "M0_P38") (pintype "bidirectional"))
      (node (ref "U1") (pin "P39") (pinfunction "M2_P39") (pintype "bidirectional"))
      (node (ref "U1") (pin "P42") (pinfunction "GND4_P42") (pintype "passive"))
      (node (ref "U1") (pin "P45") (pinfunction "GND5_P45") (pintype "passive"))
      (node (ref "U1") (pin "P64") (pinfunction "GND6_P64") (pintype "passive"))
      (node (ref "U1") (pin "P67") (pinfunction "GND7_P67") (pintype "passive"))
      (node (ref "U1") (pin "P81") (pinfunction "GND8_P81") (pintype "passive"))
      (node (ref "U1") (pin "P88") (pinfunction "GND9_P88") (pintype "passive"))
      (node (ref "U1") (pin "P9") (pinfunction "GND0_P9") (pintype "passive"))
      (node (ref "U1") (pin "P94") (pinfunction "GND10_P94") (pintype "passive"))
      (node (ref "WR_PROT") (pin "1") (pinfunction "1_1") (pintype "passive"))
      (node (ref "X1") (pin "3") (pinfunction "2_3") (pintype "passive"))
      (node (ref "X2") (pin "13") (pinfunction "13_13") (pintype "passive"))
      (node (ref "X2") (pin "14") (pinfunction "14_14") (pintype "passive"))
      (node (ref "X2") (pin "17") (pinfunction "17_17") (pintype "passive"))
      (node (ref "X2") (pin "18") (pinfunction "18_18") (pintype "passive"))
      (node (ref "X2") (pin "21") (pinfunction "21_21") (pintype "passive"))
      (node (ref "X2") (pin "4") (pinfunction "4_4") (pintype "passive"))
      (node (ref "X2") (pin "5") (pinfunction "5_5") (pintype "passive"))
      (node (ref "X2") (pin "9") (pinfunction "9_9") (pintype "passive"))
      (node (ref "X3") (pin "3") (pinfunction "3_3") (pintype "passive"))
      (node (ref "X3") (pin "SH2") (pinfunction "PE2_SH2") (pintype "power_in"))
      (node (ref "X4") (pin "8") (pinfunction "F_8") (pintype "passive"))
      (node (ref "X4") (pin "G1") (pinfunction "G1_G1") (pintype "passive"))
      (node (ref "X5") (pin "8") (pinfunction "F_8") (pintype "passive"))
      (node (ref "X5") (pin "G1") (pinfunction "G1_G1") (pintype "passive"))
    )
    (net (code "66") (name "Net-(C1-Pad2)") (class "Default")
      (node (ref "C1") (pin "2") (pinfunction "2_2") (pintype "passive"))
      (node (ref "R23") (pin "2") (pinfunction "2_2") (pintype "passive"))
      (node (ref "R48") (pin "1") (pinfunction "1_1") (pintype "passive"))
    )
    (net (code "67") (name "Net-(C2-Pad1)") (class "Default")
      (node (ref "C2") (pin "1") (pinfunction "1_1") (pintype "passive"))
      (node (ref "R17") (pin "2") (pinfunction "2_2") (pintype "passive"))
      (node (ref "X1") (pin "1") (pinfunction "1_1") (pintype "passive"))
    )
    (net (code "68") (name "Net-(C3-Pad1)") (class "Default")
      (node (ref "C3") (pin "1") (pinfunction "1_1") (pintype "passive"))
      (node (ref "R48") (pin "2") (pinfunction "2_2") (pintype "passive"))
    )
    (net (code "69") (name "Net-(C4-Pad1)") (class "Default")
      (node (ref "C4") (pin "1") (pinfunction "1_1") (pintype "passive"))
      (node (ref "R49") (pin "2") (pinfunction "2_2") (pintype "passive"))
    )
    (net (code "70") (name "Net-(C5-Pad2)") (class "Default")
      (node (ref "C5") (pin "2") (pinfunction "2_2") (pintype "passive"))
      (node (ref "R34") (pin "2") (pinfunction "2_2") (pintype "passive"))
      (node (ref "R49") (pin "1") (pinfunction "1_1") (pintype "passive"))
    )
    (net (code "71") (name "Net-(IC1-CLK)") (class "Default")
      (node (ref "IC1") (pin "3") (pinfunction "CLK_3") (pintype "bidirectional"))
      (node (ref "U1") (pin "P72") (pinfunction "CCLK_P72") (pintype "bidirectional"))
    )
    (net (code "72") (name "Net-(IC1-TDO)") (class "Default")
      (node (ref "IC1") (pin "17") (pinfunction "TDO_17") (pintype "bidirectional"))
      (node (ref "R1") (pin "2") (pinfunction "2_2") (pintype "passive"))
    )
    (net (code "73") (name "Net-(IC1-{slash}CE)") (class "Default")
      (node (ref "IC1") (pin "10") (pinfunction "/CE_10") (pintype "bidirectional"))
      (node (ref "U1") (pin "P71") (pinfunction "DONE_P71") (pintype "bidirectional"))
    )
    (net (code "74") (name "Net-(IC1-{slash}CF)") (class "Default")
      (node (ref "IC1") (pin "7") (pinfunction "/CF_7") (pintype "bidirectional"))
      (node (ref "U1") (pin "P143") (pinfunction "PROG_B_P143") (pintype "bidirectional"))
    )
    (net (code "75") (name "Net-(IC2-~{WP})") (class "Default")
      (node (ref "IC2") (pin "3") (pinfunction "~{WP}_3") (pintype "input"))
      (node (ref "R47") (pin "1") (pinfunction "1_1") (pintype "passive"))
      (node (ref "WR_PROT") (pin "2") (pinfunction "2_2") (pintype "passive"))
    )
    (net (code "76") (name "Net-(Q5-B)") (class "Default")
      (node (ref "Q5") (pin "1") (pinfunction "B_1") (pintype "passive"))
      (node (ref "R8") (pin "2") (pinfunction "2_2") (pintype "passive"))
    )
    (net (code "77") (name "Net-(Q5-E)") (class "Default")
      (node (ref "Q5") (pin "2") (pinfunction "E_2") (pintype "passive"))
      (node (ref "R13") (pin "2") (pinfunction "2_2") (pintype "passive"))
      (node (ref "R14") (pin "2") (pinfunction "2_2") (pintype "passive"))
    )
    (net (code "78") (name "Net-(Q6-B)") (class "Default")
      (node (ref "Q6") (pin "1") (pinfunction "B_1") (pintype "passive"))
      (node (ref "R10") (pin "2") (pinfunction "2_2") (pintype "passive"))
      (node (ref "R9") (pin "2") (pinfunction "2_2") (pintype "passive"))
    )
    (net (code "79") (name "Net-(Q6-E)") (class "Default")
      (node (ref "Q6") (pin "2") (pinfunction "E_2") (pintype "passive"))
      (node (ref "R15") (pin "2") (pinfunction "2_2") (pintype "passive"))
      (node (ref "R16") (pin "2") (pinfunction "2_2") (pintype "passive"))
      (node (ref "R20") (pin "2") (pinfunction "2_2") (pintype "passive"))
    )
    (net (code "80") (name "Net-(Q7-B)") (class "Default")
      (node (ref "Q7") (pin "1") (pinfunction "B_1") (pintype "passive"))
      (node (ref "R29") (pin "2") (pinfunction "2_2") (pintype "passive"))
      (node (ref "R30") (pin "2") (pinfunction "2_2") (pintype "passive"))
    )
    (net (code "81") (name "Net-(Q7-E)") (class "Default")
      (node (ref "Q7") (pin "2") (pinfunction "E_2") (pintype "passive"))
      (node (ref "R31") (pin "2") (pinfunction "2_2") (pintype "passive"))
      (node (ref "R32") (pin "2") (pinfunction "2_2") (pintype "passive"))
      (node (ref "R33") (pin "2") (pinfunction "2_2") (pintype "passive"))
    )
    (net (code "82") (name "Net-(Q8-B)") (class "Default")
      (node (ref "Q8") (pin "1") (pinfunction "B_1") (pintype "passive"))
      (node (ref "R24") (pin "2") (pinfunction "2_2") (pintype "passive"))
      (node (ref "R25") (pin "2") (pinfunction "2_2") (pintype "passive"))
    )
    (net (code "83") (name "Net-(Q8-E)") (class "Default")
      (node (ref "Q8") (pin "2") (pinfunction "E_2") (pintype "passive"))
      (node (ref "R26") (pin "2") (pinfunction "2_2") (pintype "passive"))
      (node (ref "R27") (pin "2") (pinfunction "2_2") (pintype "passive"))
      (node (ref "R28") (pin "2") (pinfunction "2_2") (pintype "passive"))
    )
    (net (code "84") (name "Net-(R18-Pad2)") (class "Default")
      (node (ref "R18") (pin "2") (pinfunction "2_2") (pintype "passive"))
      (node (ref "R22") (pin "2") (pinfunction "2_2") (pintype "passive"))
    )
    (net (code "85") (name "Net-(R51-Pad2)") (class "Default")
      (node (ref "R51") (pin "2") (pinfunction "2_2") (pintype "passive"))
      (node (ref "SJ2") (pin "2") (pinfunction "2_2") (pintype "passive"))
    )
    (net (code "86") (name "Net-(T2-B)") (class "Default")
      (node (ref "C2") (pin "2") (pinfunction "2_2") (pintype "passive"))
      (node (ref "R18") (pin "1") (pinfunction "1_1") (pintype "passive"))
      (node (ref "R19") (pin "2") (pinfunction "2_2") (pintype "passive"))
      (node (ref "T2") (pin "1") (pinfunction "B_1") (pintype "passive"))
    )
    (net (code "87") (name "Net-(U$1-A0)") (class "Default")
      (node (ref "U$1") (pin "P20") (pinfunction "A0_P20") (pintype "bidirectional"))
      (node (ref "U1") (pin "P77") (pinfunction "IO_L20P_3_P77") (pintype "bidirectional"))
    )
    (net (code "88") (name "Net-(U$1-A1)") (class "Default")
      (node (ref "U$1") (pin "P19") (pinfunction "A1_P19") (pintype "bidirectional"))
      (node (ref "U1") (pin "P76") (pinfunction "IO_P76") (pintype "bidirectional"))
    )
    (net (code "89") (name "Net-(U$1-A2)") (class "Default")
      (node (ref "U$1") (pin "P18") (pinfunction "A2_P18") (pintype "bidirectional"))
      (node (ref "U1") (pin "P74") (pinfunction "IO_L01N_3VRP_3_P74") (pintype "bidirectional"))
    )
    (net (code "90") (name "Net-(U$1-A3)") (class "Default")
      (node (ref "U$1") (pin "P17") (pinfunction "A3_P17") (pintype "bidirectional"))
      (node (ref "U1") (pin "P73") (pinfunction "IO_L01P_3VRN_3_P73") (pintype "bidirectional"))
    )
    (net (code "91") (name "Net-(U$1-A4)") (class "Default")
      (node (ref "U$1") (pin "P16") (pinfunction "A4_P16") (pintype "bidirectional"))
      (node (ref "U1") (pin "P108") (pinfunction "IO_L01N_2VRP_2_P108") (pintype "bidirectional"))
    )
    (net (code "92") (name "Net-(U$1-A5)") (class "Default")
      (node (ref "U$1") (pin "P15") (pinfunction "A5_P15") (pintype "bidirectional"))
      (node (ref "U1") (pin "P107") (pinfunction "IO_L01P_2VRN_2_P107") (pintype "bidirectional"))
    )
    (net (code "93") (name "Net-(U$1-A6)") (class "Default")
      (node (ref "U$1") (pin "P14") (pinfunction "A6_P14") (pintype "bidirectional"))
      (node (ref "U1") (pin "P105") (pinfunction "IO_L20N_2_P105") (pintype "bidirectional"))
    )
    (net (code "94") (name "Net-(U$1-A7)") (class "Default")
      (node (ref "U$1") (pin "P13") (pinfunction "A7_P13") (pintype "bidirectional"))
      (node (ref "U1") (pin "P104") (pinfunction "IO_L20P_2_P104") (pintype "bidirectional"))
    )
    (net (code "95") (name "Net-(U$1-A8)") (class "Default")
      (node (ref "U$1") (pin "P3") (pinfunction "A8_P3") (pintype "bidirectional"))
      (node (ref "U1") (pin "P93") (pinfunction "IO_L40N_2_P93") (pintype "bidirectional"))
    )
    (net (code "96") (name "Net-(U$1-A9)") (class "Default")
      (node (ref "U$1") (pin "P2") (pinfunction "A9_P2") (pintype "bidirectional"))
      (node (ref "U1") (pin "P92") (pinfunction "IO_L40P_2VREF_2_P92") (pintype "bidirectional"))
    )
    (net (code "97") (name "Net-(U$1-A10)") (class "Default")
      (node (ref "U$1") (pin "P31") (pinfunction "A10_P31") (pintype "bidirectional"))
      (node (ref "U1") (pin "P87") (pinfunction "IO_L24N_3_P87") (pintype "bidirectional"))
    )
    (net (code "98") (name "Net-(U$1-A11)") (class "Default")
      (node (ref "U$1") (pin "P1") (pinfunction "A11_P1") (pintype "bidirectional"))
      (node (ref "U1") (pin "P90") (pinfunction "IO_L40N_3VREF_3_P90") (pintype "bidirectional"))
    )
    (net (code "99") (name "Net-(U$1-A12)") (class "Default")
      (node (ref "U$1") (pin "P12") (pinfunction "A12_P12") (pintype "bidirectional"))
      (node (ref "U1") (pin "P103") (pinfunction "IO_L21N_2_P103") (pintype "bidirectional"))
    )
    (net (code "100") (name "Net-(U$1-A13)") (class "Default")
      (node (ref "U$1") (pin "P4") (pinfunction "A13_P4") (pintype "bidirectional"))
      (node (ref "U1") (pin "P95") (pinfunction "IO_L24P_2_P95") (pintype "bidirectional"))
    )
    (net (code "101") (name "Net-(U$1-A14)") (class "Default")
      (node (ref "U$1") (pin "P11") (pinfunction "A14_P11") (pintype "bidirectional"))
      (node (ref "U1") (pin "P102") (pinfunction "IO_L21P_2_P102") (pintype "bidirectional"))
    )
    (net (code "102") (name "Net-(U$1-A15)") (class "Default")
      (node (ref "U$1") (pin "P7") (pinfunction "A15_P7") (pintype "bidirectional"))
      (node (ref "U1") (pin "P98") (pinfunction "IO_L23N_2VREF_2_P98") (pintype "bidirectional"))
    )
    (net (code "103") (name "Net-(U$1-A16)") (class "Default")
      (node (ref "U$1") (pin "P10") (pinfunction "A16_P10") (pintype "bidirectional"))
      (node (ref "U1") (pin "P100") (pinfunction "IO_L22N_2_P100") (pintype "bidirectional"))
    )
    (net (code "104") (name "Net-(U$1-A17)") (class "Default")
      (node (ref "U$1") (pin "P6") (pinfunction "A17_P6") (pintype "bidirectional"))
      (node (ref "U1") (pin "P97") (pinfunction "IO_L23P_2_P97") (pintype "bidirectional"))
    )
    (net (code "105") (name "Net-(U$1-A18)") (class "Default")
      (node (ref "U$1") (pin "P9") (pinfunction "A18_P9") (pintype "bidirectional"))
      (node (ref "U1") (pin "P99") (pinfunction "IO_L22P_2_P99") (pintype "bidirectional"))
    )
    (net (code "106") (name "Net-(U$1-DQ0)") (class "Default")
      (node (ref "U$1") (pin "P21") (pinfunction "DQ0_P21") (pintype "bidirectional"))
      (node (ref "U1") (pin "P78") (pinfunction "IO_L20N_3_P78") (pintype "bidirectional"))
    )
    (net (code "107") (name "Net-(U$1-DQ1)") (class "Default")
      (node (ref "U$1") (pin "P22") (pinfunction "DQ1_P22") (pintype "bidirectional"))
      (node (ref "U1") (pin "P79") (pinfunction "IO_L21P_3_P79") (pintype "bidirectional"))
    )
    (net (code "108") (name "Net-(U$1-DQ2)") (class "Default")
      (node (ref "U$1") (pin "P23") (pinfunction "DQ2_P23") (pintype "bidirectional"))
      (node (ref "U1") (pin "P80") (pinfunction "IO_L21N_3_P80") (pintype "bidirectional"))
    )
    (net (code "109") (name "Net-(U$1-DQ3)") (class "Default")
      (node (ref "U$1") (pin "P25") (pinfunction "DQ3_P25") (pintype "bidirectional"))
      (node (ref "U1") (pin "P82") (pinfunction "IO_L22P_3_P82") (pintype "bidirectional"))
    )
    (net (code "110") (name "Net-(U$1-DQ4)") (class "Default")
      (node (ref "U$1") (pin "P26") (pinfunction "DQ4_P26") (pintype "bidirectional"))
      (node (ref "U1") (pin "P83") (pinfunction "IO_L22N_3_P83") (pintype "bidirectional"))
    )
    (net (code "111") (name "Net-(U$1-DQ5)") (class "Default")
      (node (ref "U$1") (pin "P27") (pinfunction "DQ5_P27") (pintype "bidirectional"))
      (node (ref "U1") (pin "P84") (pinfunction "IO_L23P_3VREF_3_P84") (pintype "bidirectional"))
    )
    (net (code "112") (name "Net-(U$1-DQ6)") (class "Default")
      (node (ref "U$1") (pin "P28") (pinfunction "DQ6_P28") (pintype "bidirectional"))
      (node (ref "U1") (pin "P85") (pinfunction "IO_L23N_3_P85") (pintype "bidirectional"))
    )
    (net (code "113") (name "Net-(U$1-DQ7)") (class "Default")
      (node (ref "U$1") (pin "P29") (pinfunction "DQ7_P29") (pintype "bidirectional"))
      (node (ref "U1") (pin "P86") (pinfunction "IO_L24P_3_P86") (pintype "bidirectional"))
    )
    (net (code "114") (name "Net-(U$1-OE)") (class "Default")
      (node (ref "U$1") (pin "P32") (pinfunction "OE_P32") (pintype "bidirectional"))
      (node (ref "U1") (pin "P89") (pinfunction "IO_L40P_3_P89") (pintype "bidirectional"))
    )
    (net (code "115") (name "Net-(U$1-WE)") (class "Default")
      (node (ref "U$1") (pin "P5") (pinfunction "WE_P5") (pintype "bidirectional"))
      (node (ref "U1") (pin "P96") (pinfunction "IO_L24N_2_P96") (pintype "bidirectional"))
    )
    (net (code "116") (name "Net-(U1N-TCK)") (class "Default")
      (node (ref "R2") (pin "1") (pinfunction "1_1") (pintype "passive"))
      (node (ref "U1") (pin "P110") (pinfunction "TCK_P110") (pintype "bidirectional"))
    )
    (net (code "117") (name "Net-(U1N-TDI)") (class "Default")
      (node (ref "R1") (pin "1") (pinfunction "1_1") (pintype "passive"))
      (node (ref "U1") (pin "P144") (pinfunction "TDI_P144") (pintype "bidirectional"))
    )
    (net (code "118") (name "Net-(U1N-TMS)") (class "Default")
      (node (ref "R3") (pin "1") (pinfunction "1_1") (pintype "passive"))
      (node (ref "U1") (pin "P111") (pinfunction "TMS_P111") (pintype "bidirectional"))
    )
    (net (code "119") (name "Net-(X4A-F)") (class "Default")
      (node (ref "R40") (pin "2") (pinfunction "2_2") (pintype "passive"))
      (node (ref "X4") (pin "1") (pinfunction "F_1") (pintype "passive"))
    )
    (net (code "120") (name "Net-(X4B-F)") (class "Default")
      (node (ref "R41") (pin "2") (pinfunction "2_2") (pintype "passive"))
      (node (ref "X4") (pin "2") (pinfunction "F_2") (pintype "passive"))
    )
    (net (code "121") (name "Net-(X4C-F)") (class "Default")
      (node (ref "R42") (pin "2") (pinfunction "2_2") (pintype "passive"))
      (node (ref "X4") (pin "3") (pinfunction "F_3") (pintype "passive"))
    )
    (net (code "122") (name "Net-(X4D-F)") (class "Default")
      (node (ref "R43") (pin "2") (pinfunction "2_2") (pintype "passive"))
      (node (ref "X4") (pin "4") (pinfunction "F_4") (pintype "passive"))
    )
    (net (code "123") (name "Net-(X4F-F)") (class "Default")
      (node (ref "R44") (pin "2") (pinfunction "2_2") (pintype "passive"))
      (node (ref "X4") (pin "6") (pinfunction "F_6") (pintype "passive"))
    )
    (net (code "124") (name "Net-(X4G-F)") (class "Default")
      (node (ref "R45") (pin "2") (pinfunction "2_2") (pintype "passive"))
      (node (ref "X4") (pin "7") (pinfunction "F_7") (pintype "passive"))
    )
    (net (code "125") (name "Net-(X5A-F)") (class "Default")
      (node (ref "R46") (pin "1") (pinfunction "1_1") (pintype "passive"))
      (node (ref "X5") (pin "1") (pinfunction "F_1") (pintype "passive"))
    )
    (net (code "126") (name "Net-(X5B-F)") (class "Default")
      (node (ref "R39") (pin "1") (pinfunction "1_1") (pintype "passive"))
      (node (ref "X5") (pin "2") (pinfunction "F_2") (pintype "passive"))
    )
    (net (code "127") (name "Net-(X5C-F)") (class "Default")
      (node (ref "R38") (pin "1") (pinfunction "1_1") (pintype "passive"))
      (node (ref "X5") (pin "3") (pinfunction "F_3") (pintype "passive"))
    )
    (net (code "128") (name "Net-(X5D-F)") (class "Default")
      (node (ref "R37") (pin "1") (pinfunction "1_1") (pintype "passive"))
      (node (ref "X5") (pin "4") (pinfunction "F_4") (pintype "passive"))
    )
    (net (code "129") (name "Net-(X5F-F)") (class "Default")
      (node (ref "R36") (pin "1") (pinfunction "1_1") (pintype "passive"))
      (node (ref "X5") (pin "6") (pinfunction "F_6") (pintype "passive"))
    )
    (net (code "130") (name "Net-(X5G-F)") (class "Default")
      (node (ref "R35") (pin "1") (pinfunction "1_1") (pintype "passive"))
      (node (ref "X5") (pin "7") (pinfunction "F_7") (pintype "passive"))
    )
    (net (code "131") (name "unconnected-(IC1-NC.1-Pad2)") (class "Default")
      (node (ref "IC1") (pin "2") (pinfunction "NC.1_2") (pintype "bidirectional"))
    )
    (net (code "132") (name "unconnected-(IC1-NC.2-Pad9)") (class "Default")
      (node (ref "IC1") (pin "9") (pinfunction "NC.2_9") (pintype "bidirectional"))
    )
    (net (code "133") (name "unconnected-(IC1-NC.3-Pad12)") (class "Default")
      (node (ref "IC1") (pin "12") (pinfunction "NC.3_12") (pintype "bidirectional"))
    )
    (net (code "134") (name "unconnected-(IC1-NC.4-Pad14)") (class "Default")
      (node (ref "IC1") (pin "14") (pinfunction "NC.4_14") (pintype "bidirectional"))
    )
    (net (code "135") (name "unconnected-(IC1-NC.5-Pad15)") (class "Default")
      (node (ref "IC1") (pin "15") (pinfunction "NC.5_15") (pintype "bidirectional"))
    )
    (net (code "136") (name "unconnected-(IC1-NC.6-Pad16)") (class "Default")
      (node (ref "IC1") (pin "16") (pinfunction "NC.6_16") (pintype "bidirectional"))
    )
    (net (code "137") (name "unconnected-(IC1-{slash}CEO-Pad13)") (class "Default")
      (node (ref "IC1") (pin "13") (pinfunction "/CEO_13") (pintype "bidirectional"))
    )
    (net (code "138") (name "unconnected-(REG1.2-VOUT2-Pad2)") (class "Default")
      (node (ref "REG1.2") (pin "2") (pinfunction "VOUT2_2") (pintype "bidirectional"))
    )
    (net (code "139") (name "unconnected-(U$2-TRI-PadENA)") (class "Default")
      (node (ref "U$2") (pin "ENA") (pinfunction "TRI_ENA") (pintype "input"))
    )
    (net (code "140") (name "unconnected-(U$3-AREF-Pad42)") (class "Default")
      (node (ref "U$3") (pin "42") (pinfunction "AREF_42") (pintype "bidirectional"))
    )
    (net (code "141") (name "unconnected-(U$3-AVCC-Pad24)") (class "Default")
      (node (ref "U$3") (pin "24") (pinfunction "AVCC_24") (pintype "bidirectional"))
    )
    (net (code "142") (name "unconnected-(U$3-AVCC1-Pad44)") (class "Default")
      (node (ref "U$3") (pin "44") (pinfunction "AVCC1_44") (pintype "bidirectional"))
    )
    (net (code "143") (name "unconnected-(U$3-D+-Pad4)") (class "Default")
      (node (ref "U$3") (pin "4") (pinfunction "D+_4") (pintype "bidirectional"))
    )
    (net (code "144") (name "unconnected-(U$3-D--Pad3)") (class "Default")
      (node (ref "U$3") (pin "3") (pinfunction "D-_3") (pintype "bidirectional"))
    )
    (net (code "145") (name "unconnected-(U$3-GND-Pad15)") (class "Default")
      (node (ref "U$3") (pin "15") (pinfunction "GND_15") (pintype "bidirectional"))
    )
    (net (code "146") (name "unconnected-(U$3-GND1-Pad23)") (class "Default")
      (node (ref "U$3") (pin "23") (pinfunction "GND1_23") (pintype "bidirectional"))
    )
    (net (code "147") (name "unconnected-(U$3-GND2-Pad35)") (class "Default")
      (node (ref "U$3") (pin "35") (pinfunction "GND2_35") (pintype "bidirectional"))
    )
    (net (code "148") (name "unconnected-(U$3-GND3-Pad43)") (class "Default")
      (node (ref "U$3") (pin "43") (pinfunction "GND3_43") (pintype "bidirectional"))
    )
    (net (code "149") (name "unconnected-(U$3-PB4(ADC11)-Pad28)") (class "Default")
      (node (ref "U$3") (pin "28") (pinfunction "PB4(ADC11)_28") (pintype "bidirectional"))
    )
    (net (code "150") (name "unconnected-(U$3-PB5(OC1A{slash}ADC12{slash}~{OC4B})-Pad29)") (class "Default")
      (node (ref "U$3") (pin "29") (pinfunction "PB5(OC1A/ADC12/~{OC4B})_29") (pintype "bidirectional"))
    )
    (net (code "151") (name "unconnected-(U$3-PB6(OC1B{slash}OC4B{slash}ADC13)-Pad30)") (class "Default")
      (node (ref "U$3") (pin "30") (pinfunction "PB6(OC1B/OC4B/ADC13)_30") (pintype "bidirectional"))
    )
    (net (code "152") (name "unconnected-(U$3-PB7(OC0A{slash}OC1C{slash}RTS)-Pad12)") (class "Default")
      (node (ref "U$3") (pin "12") (pinfunction "PB7(OC0A/OC1C/RTS)_12") (pintype "bidirectional"))
    )
    (net (code "153") (name "unconnected-(U$3-PC6(OC3A{slash}~{OC4A})-Pad31)") (class "Default")
      (node (ref "U$3") (pin "31") (pinfunction "PC6(OC3A/~{OC4A})_31") (pintype "bidirectional"))
    )
    (net (code "154") (name "unconnected-(U$3-PC7(ICP3{slash}CLK0{slash}OC4A)-Pad32)") (class "Default")
      (node (ref "U$3") (pin "32") (pinfunction "PC7(ICP3/CLK0/OC4A)_32") (pintype "bidirectional"))
    )
    (net (code "155") (name "unconnected-(U$3-PD0(INT0{slash}OC0B{slash}SCL)-Pad18)") (class "Default")
      (node (ref "U$3") (pin "18") (pinfunction "PD0(INT0/OC0B/SCL)_18") (pintype "bidirectional"))
    )
    (net (code "156") (name "unconnected-(U$3-PD1(INT1{slash}SDA)-Pad19)") (class "Default")
      (node (ref "U$3") (pin "19") (pinfunction "PD1(INT1/SDA)_19") (pintype "bidirectional"))
    )
    (net (code "157") (name "unconnected-(U$3-PD2(INT2{slash}RXD1)-Pad20)") (class "Default")
      (node (ref "U$3") (pin "20") (pinfunction "PD2(INT2/RXD1)_20") (pintype "bidirectional"))
    )
    (net (code "158") (name "unconnected-(U$3-PD3(INT3{slash}TXD1)-Pad21)") (class "Default")
      (node (ref "U$3") (pin "21") (pinfunction "PD3(INT3/TXD1)_21") (pintype "bidirectional"))
    )
    (net (code "159") (name "unconnected-(U$3-PD4(ICP1{slash}ADC8)-Pad25)") (class "Default")
      (node (ref "U$3") (pin "25") (pinfunction "PD4(ICP1/ADC8)_25") (pintype "bidirectional"))
    )
    (net (code "160") (name "unconnected-(U$3-PD5(XCK{slash}CTS)-Pad22)") (class "Default")
      (node (ref "U$3") (pin "22") (pinfunction "PD5(XCK/CTS)_22") (pintype "bidirectional"))
    )
    (net (code "161") (name "unconnected-(U$3-PD6(T1{slash}ADC9{slash}~{OC4D})-Pad26)") (class "Default")
      (node (ref "U$3") (pin "26") (pinfunction "PD6(T1/ADC9/~{OC4D})_26") (pintype "bidirectional"))
    )
    (net (code "162") (name "unconnected-(U$3-PD7(OC4D{slash}ADC10{slash}T0)-Pad27)") (class "Default")
      (node (ref "U$3") (pin "27") (pinfunction "PD7(OC4D/ADC10/T0)_27") (pintype "bidirectional"))
    )
    (net (code "163") (name "unconnected-(U$3-PE2(~{HWB})-Pad33)") (class "Default")
      (node (ref "U$3") (pin "33") (pinfunction "PE2(~{HWB})_33") (pintype "bidirectional"))
    )
    (net (code "164") (name "unconnected-(U$3-PE6(INT.6{slash}AIN0)-Pad1)") (class "Default")
      (node (ref "U$3") (pin "1") (pinfunction "PE6(INT.6/AIN0)_1") (pintype "bidirectional"))
    )
    (net (code "165") (name "unconnected-(U$3-PF0(ADC0)-Pad41)") (class "Default")
      (node (ref "U$3") (pin "41") (pinfunction "PF0(ADC0)_41") (pintype "bidirectional"))
    )
    (net (code "166") (name "unconnected-(U$3-PF1(ADC1)-Pad40)") (class "Default")
      (node (ref "U$3") (pin "40") (pinfunction "PF1(ADC1)_40") (pintype "bidirectional"))
    )
    (net (code "167") (name "unconnected-(U$3-UCAP-Pad6)") (class "Default")
      (node (ref "U$3") (pin "6") (pinfunction "UCAP_6") (pintype "bidirectional"))
    )
    (net (code "168") (name "unconnected-(U$3-UGND-Pad5)") (class "Default")
      (node (ref "U$3") (pin "5") (pinfunction "UGND_5") (pintype "bidirectional"))
    )
    (net (code "169") (name "unconnected-(U$3-UVCC-Pad2)") (class "Default")
      (node (ref "U$3") (pin "2") (pinfunction "UVCC_2") (pintype "bidirectional"))
    )
    (net (code "170") (name "unconnected-(U$3-VBUS-Pad7)") (class "Default")
      (node (ref "U$3") (pin "7") (pinfunction "VBUS_7") (pintype "bidirectional"))
    )
    (net (code "171") (name "unconnected-(U$3-VCC-Pad14)") (class "Default")
      (node (ref "U$3") (pin "14") (pinfunction "VCC_14") (pintype "bidirectional"))
    )
    (net (code "172") (name "unconnected-(U$3-VCC1-Pad34)") (class "Default")
      (node (ref "U$3") (pin "34") (pinfunction "VCC1_34") (pintype "bidirectional"))
    )
    (net (code "173") (name "unconnected-(U$3-XTAL1-Pad17)") (class "Default")
      (node (ref "U$3") (pin "17") (pinfunction "XTAL1_17") (pintype "bidirectional"))
    )
    (net (code "174") (name "unconnected-(U$3-XTAL2-Pad16)") (class "Default")
      (node (ref "U$3") (pin "16") (pinfunction "XTAL2_16") (pintype "bidirectional"))
    )
    (net (code "175") (name "unconnected-(U$3-{slash}RESET-Pad13)") (class "Default")
      (node (ref "U$3") (pin "13") (pinfunction "/RESET_13") (pintype "bidirectional"))
    )
    (net (code "176") (name "unconnected-(U1A-IO_L27P_0-PadP135)") (class "Default")
      (node (ref "U1") (pin "P135") (pinfunction "IO_L27P_0_P135") (pintype "bidirectional"))
    )
    (net (code "177") (name "unconnected-(U1A-IO_L30N_0-PadP132)") (class "Default")
      (node (ref "U1") (pin "P132") (pinfunction "IO_L30N_0_P132") (pintype "bidirectional"))
    )
    (net (code "178") (name "unconnected-(U1A-IO_L30P_0-PadP131)") (class "Default")
      (node (ref "U1") (pin "P131") (pinfunction "IO_L30P_0_P131") (pintype "bidirectional"))
    )
    (net (code "179") (name "unconnected-(U1A-IO_L31N_0-PadP130)") (class "Default")
      (node (ref "U1") (pin "P130") (pinfunction "IO_L31N_0_P130") (pintype "bidirectional"))
    )
    (net (code "180") (name "unconnected-(U1A-IO_L31P_0VREF_0-PadP129)") (class "Default")
      (node (ref "U1") (pin "P129") (pinfunction "IO_L31P_0VREF_0_P129") (pintype "bidirectional"))
    )
    (net (code "181") (name "unconnected-(U1A-IO_L32N_0GCLK7-PadP128)") (class "Default")
      (node (ref "U1") (pin "P128") (pinfunction "IO_L32N_0GCLK7_P128") (pintype "bidirectional"))
    )
    (net (code "182") (name "unconnected-(U1A-IO_L32P_0GCLK6-PadP127)") (class "Default")
      (node (ref "U1") (pin "P127") (pinfunction "IO_L32P_0GCLK6_P127") (pintype "bidirectional"))
    )
    (net (code "183") (name "unconnected-(U1C-IO-PadP116)") (class "Default")
      (node (ref "U1") (pin "P116") (pinfunction "IO_P116") (pintype "bidirectional"))
    )
    (net (code "184") (name "unconnected-(U1C-IO_L01N_1VRP_1-PadP113)") (class "Default")
      (node (ref "U1") (pin "P113") (pinfunction "IO_L01N_1VRP_1_P113") (pintype "bidirectional"))
    )
    (net (code "185") (name "unconnected-(U1C-IO_L01P_1VRN_1-PadP112)") (class "Default")
      (node (ref "U1") (pin "P112") (pinfunction "IO_L01P_1VRN_1_P112") (pintype "bidirectional"))
    )
    (net (code "186") (name "unconnected-(U1C-IO_L28N_1-PadP119)") (class "Default")
      (node (ref "U1") (pin "P119") (pinfunction "IO_L28N_1_P119") (pintype "bidirectional"))
    )
    (net (code "187") (name "unconnected-(U1C-IO_L28P_1-PadP118)") (class "Default")
      (node (ref "U1") (pin "P118") (pinfunction "IO_L28P_1_P118") (pintype "bidirectional"))
    )
    (net (code "188") (name "unconnected-(U1C-IO_L31N_1VREF_1-PadP123)") (class "Default")
      (node (ref "U1") (pin "P123") (pinfunction "IO_L31N_1VREF_1_P123") (pintype "bidirectional"))
    )
    (net (code "189") (name "unconnected-(U1C-IO_L31P_1-PadP122)") (class "Default")
      (node (ref "U1") (pin "P122") (pinfunction "IO_L31P_1_P122") (pintype "bidirectional"))
    )
    (net (code "190") (name "unconnected-(U1C-IO_L32N_1GCLK5-PadP125)") (class "Default")
      (node (ref "U1") (pin "P125") (pinfunction "IO_L32N_1GCLK5_P125") (pintype "bidirectional"))
    )
    (net (code "191") (name "unconnected-(U1C-IO_L32P_1GCLK4-PadP124)") (class "Default")
      (node (ref "U1") (pin "P124") (pinfunction "IO_L32P_1GCLK4_P124") (pintype "bidirectional"))
    )
    (net (code "192") (name "unconnected-(U1J-IO_L01N_6VRP_6-PadP36)") (class "Default")
      (node (ref "U1") (pin "P36") (pinfunction "IO_L01N_6VRP_6_P36") (pintype "bidirectional"))
    )
    (net (code "193") (name "unconnected-(U1J-IO_L01P_6VRN_6-PadP35)") (class "Default")
      (node (ref "U1") (pin "P35") (pinfunction "IO_L01P_6VRN_6_P35") (pintype "bidirectional"))
    )
    (net (code "194") (name "unconnected-(U1J-IO_L20N_6-PadP33)") (class "Default")
      (node (ref "U1") (pin "P33") (pinfunction "IO_L20N_6_P33") (pintype "bidirectional"))
    )
    (net (code "195") (name "unconnected-(U1J-IO_L20P_6-PadP32)") (class "Default")
      (node (ref "U1") (pin "P32") (pinfunction "IO_L20P_6_P32") (pintype "bidirectional"))
    )
    (net (code "196") (name "unconnected-(U1J-IO_L21N_6-PadP31)") (class "Default")
      (node (ref "U1") (pin "P31") (pinfunction "IO_L21N_6_P31") (pintype "bidirectional"))
    )
    (net (code "197") (name "unconnected-(U1J-IO_L21P_6-PadP30)") (class "Default")
      (node (ref "U1") (pin "P30") (pinfunction "IO_L21P_6_P30") (pintype "bidirectional"))
    )
    (net (code "198") (name "unconnected-(U1J-IO_L22N_6-PadP28)") (class "Default")
      (node (ref "U1") (pin "P28") (pinfunction "IO_L22N_6_P28") (pintype "bidirectional"))
    )
    (net (code "199") (name "unconnected-(U1J-IO_L22P_6-PadP27)") (class "Default")
      (node (ref "U1") (pin "P27") (pinfunction "IO_L22P_6_P27") (pintype "bidirectional"))
    )
    (net (code "200") (name "unconnected-(U1J-IO_L23N_6-PadP26)") (class "Default")
      (node (ref "U1") (pin "P26") (pinfunction "IO_L23N_6_P26") (pintype "bidirectional"))
    )
    (net (code "201") (name "unconnected-(U1J-IO_L23P_6-PadP25)") (class "Default")
      (node (ref "U1") (pin "P25") (pinfunction "IO_L23P_6_P25") (pintype "bidirectional"))
    )
    (net (code "202") (name "unconnected-(U1J-IO_L24N_6VREF_6-PadP24)") (class "Default")
      (node (ref "U1") (pin "P24") (pinfunction "IO_L24N_6VREF_6_P24") (pintype "bidirectional"))
    )
    (net (code "203") (name "unconnected-(U1J-IO_L24P_6-PadP23)") (class "Default")
      (node (ref "U1") (pin "P23") (pinfunction "IO_L24P_6_P23") (pintype "bidirectional"))
    )
    (net (code "204") (name "unconnected-(U1J-IO_L40N_6-PadP21)") (class "Default")
      (node (ref "U1") (pin "P21") (pinfunction "IO_L40N_6_P21") (pintype "bidirectional"))
    )
    (net (code "205") (name "unconnected-(U1J-IO_L40P_6VREF_6-PadP20)") (class "Default")
      (node (ref "U1") (pin "P20") (pinfunction "IO_L40P_6VREF_6_P20") (pintype "bidirectional"))
    )
    (net (code "206") (name "unconnected-(U1L-IOVREF_7-PadP4)") (class "Default")
      (node (ref "U1") (pin "P4") (pinfunction "IOVREF_7_P4") (pintype "bidirectional"))
    )
    (net (code "207") (name "unconnected-(U1L-IO_L01N_7VRP_7-PadP2)") (class "Default")
      (node (ref "U1") (pin "P2") (pinfunction "IO_L01N_7VRP_7_P2") (pintype "bidirectional"))
    )
    (net (code "208") (name "unconnected-(U1L-IO_L01P_7VRN_7-PadP1)") (class "Default")
      (node (ref "U1") (pin "P1") (pinfunction "IO_L01P_7VRN_7_P1") (pintype "bidirectional"))
    )
    (net (code "209") (name "unconnected-(U1L-IO_L20N_7-PadP6)") (class "Default")
      (node (ref "U1") (pin "P6") (pinfunction "IO_L20N_7_P6") (pintype "bidirectional"))
    )
    (net (code "210") (name "unconnected-(U1L-IO_L20P_7-PadP5)") (class "Default")
      (node (ref "U1") (pin "P5") (pinfunction "IO_L20P_7_P5") (pintype "bidirectional"))
    )
    (net (code "211") (name "unconnected-(U1L-IO_L21N_7-PadP8)") (class "Default")
      (node (ref "U1") (pin "P8") (pinfunction "IO_L21N_7_P8") (pintype "bidirectional"))
    )
    (net (code "212") (name "unconnected-(U1L-IO_L21P_7-PadP7)") (class "Default")
      (node (ref "U1") (pin "P7") (pinfunction "IO_L21P_7_P7") (pintype "bidirectional"))
    )
    (net (code "213") (name "unconnected-(U1L-IO_L22N_7-PadP11)") (class "Default")
      (node (ref "U1") (pin "P11") (pinfunction "IO_L22N_7_P11") (pintype "bidirectional"))
    )
    (net (code "214") (name "unconnected-(U1L-IO_L22P_7-PadP10)") (class "Default")
      (node (ref "U1") (pin "P10") (pinfunction "IO_L22P_7_P10") (pintype "bidirectional"))
    )
    (net (code "215") (name "unconnected-(U1L-IO_L23N_7-PadP13)") (class "Default")
      (node (ref "U1") (pin "P13") (pinfunction "IO_L23N_7_P13") (pintype "bidirectional"))
    )
    (net (code "216") (name "unconnected-(U1L-IO_L23P_7-PadP12)") (class "Default")
      (node (ref "U1") (pin "P12") (pinfunction "IO_L23P_7_P12") (pintype "bidirectional"))
    )
    (net (code "217") (name "unconnected-(U1L-IO_L24N_7-PadP15)") (class "Default")
      (node (ref "U1") (pin "P15") (pinfunction "IO_L24N_7_P15") (pintype "bidirectional"))
    )
    (net (code "218") (name "unconnected-(U1L-IO_L24P_7-PadP14)") (class "Default")
      (node (ref "U1") (pin "P14") (pinfunction "IO_L24P_7_P14") (pintype "bidirectional"))
    )
    (net (code "219") (name "unconnected-(U1L-IO_L40N_7VREF_7-PadP18)") (class "Default")
      (node (ref "U1") (pin "P18") (pinfunction "IO_L40N_7VREF_7_P18") (pintype "bidirectional"))
    )
    (net (code "220") (name "unconnected-(U1L-IO_L40P_7-PadP17)") (class "Default")
      (node (ref "U1") (pin "P17") (pinfunction "IO_L40P_7_P17") (pintype "bidirectional"))
    )
    (net (code "221") (name "unconnected-(U1N-HSWAP_EN-PadP142)") (class "Default")
      (node (ref "U1") (pin "P142") (pinfunction "HSWAP_EN_P142") (pintype "bidirectional"))
    )
    (net (code "222") (name "unconnected-(X1-3-Pad2)") (class "Default")
      (node (ref "X1") (pin "2") (pinfunction "3_2") (pintype "passive"))
    )
    (net (code "223") (name "unconnected-(X2-Pad10)") (class "Default")
      (node (ref "X2") (pin "10") (pinfunction "10_10") (pintype "passive"))
    )
    (net (code "224") (name "unconnected-(X2-Pad12)") (class "Default")
      (node (ref "X2") (pin "12") (pinfunction "12_12") (pintype "passive"))
    )
    (net (code "225") (name "unconnected-(X3-Pad2)") (class "Default")
      (node (ref "X3") (pin "2") (pinfunction "2_2") (pintype "passive"))
    )
    (net (code "226") (name "unconnected-(X3-Pad8)") (class "Default")
      (node (ref "X3") (pin "8") (pinfunction "8_8") (pintype "passive"))
    )
    (net (code "227") (name "unconnected-(X4-PadG2)") (class "Default")
      (node (ref "X4") (pin "G2") (pinfunction "G2_G2") (pintype "passive"))
    )
    (net (code "228") (name "unconnected-(X5-PadG2)") (class "Default")
      (node (ref "X5") (pin "G2") (pinfunction "G2_G2") (pintype "passive"))
    )
  )
)
